# untitled.net
KiCad netlist of a schematic drawn in EAGLE
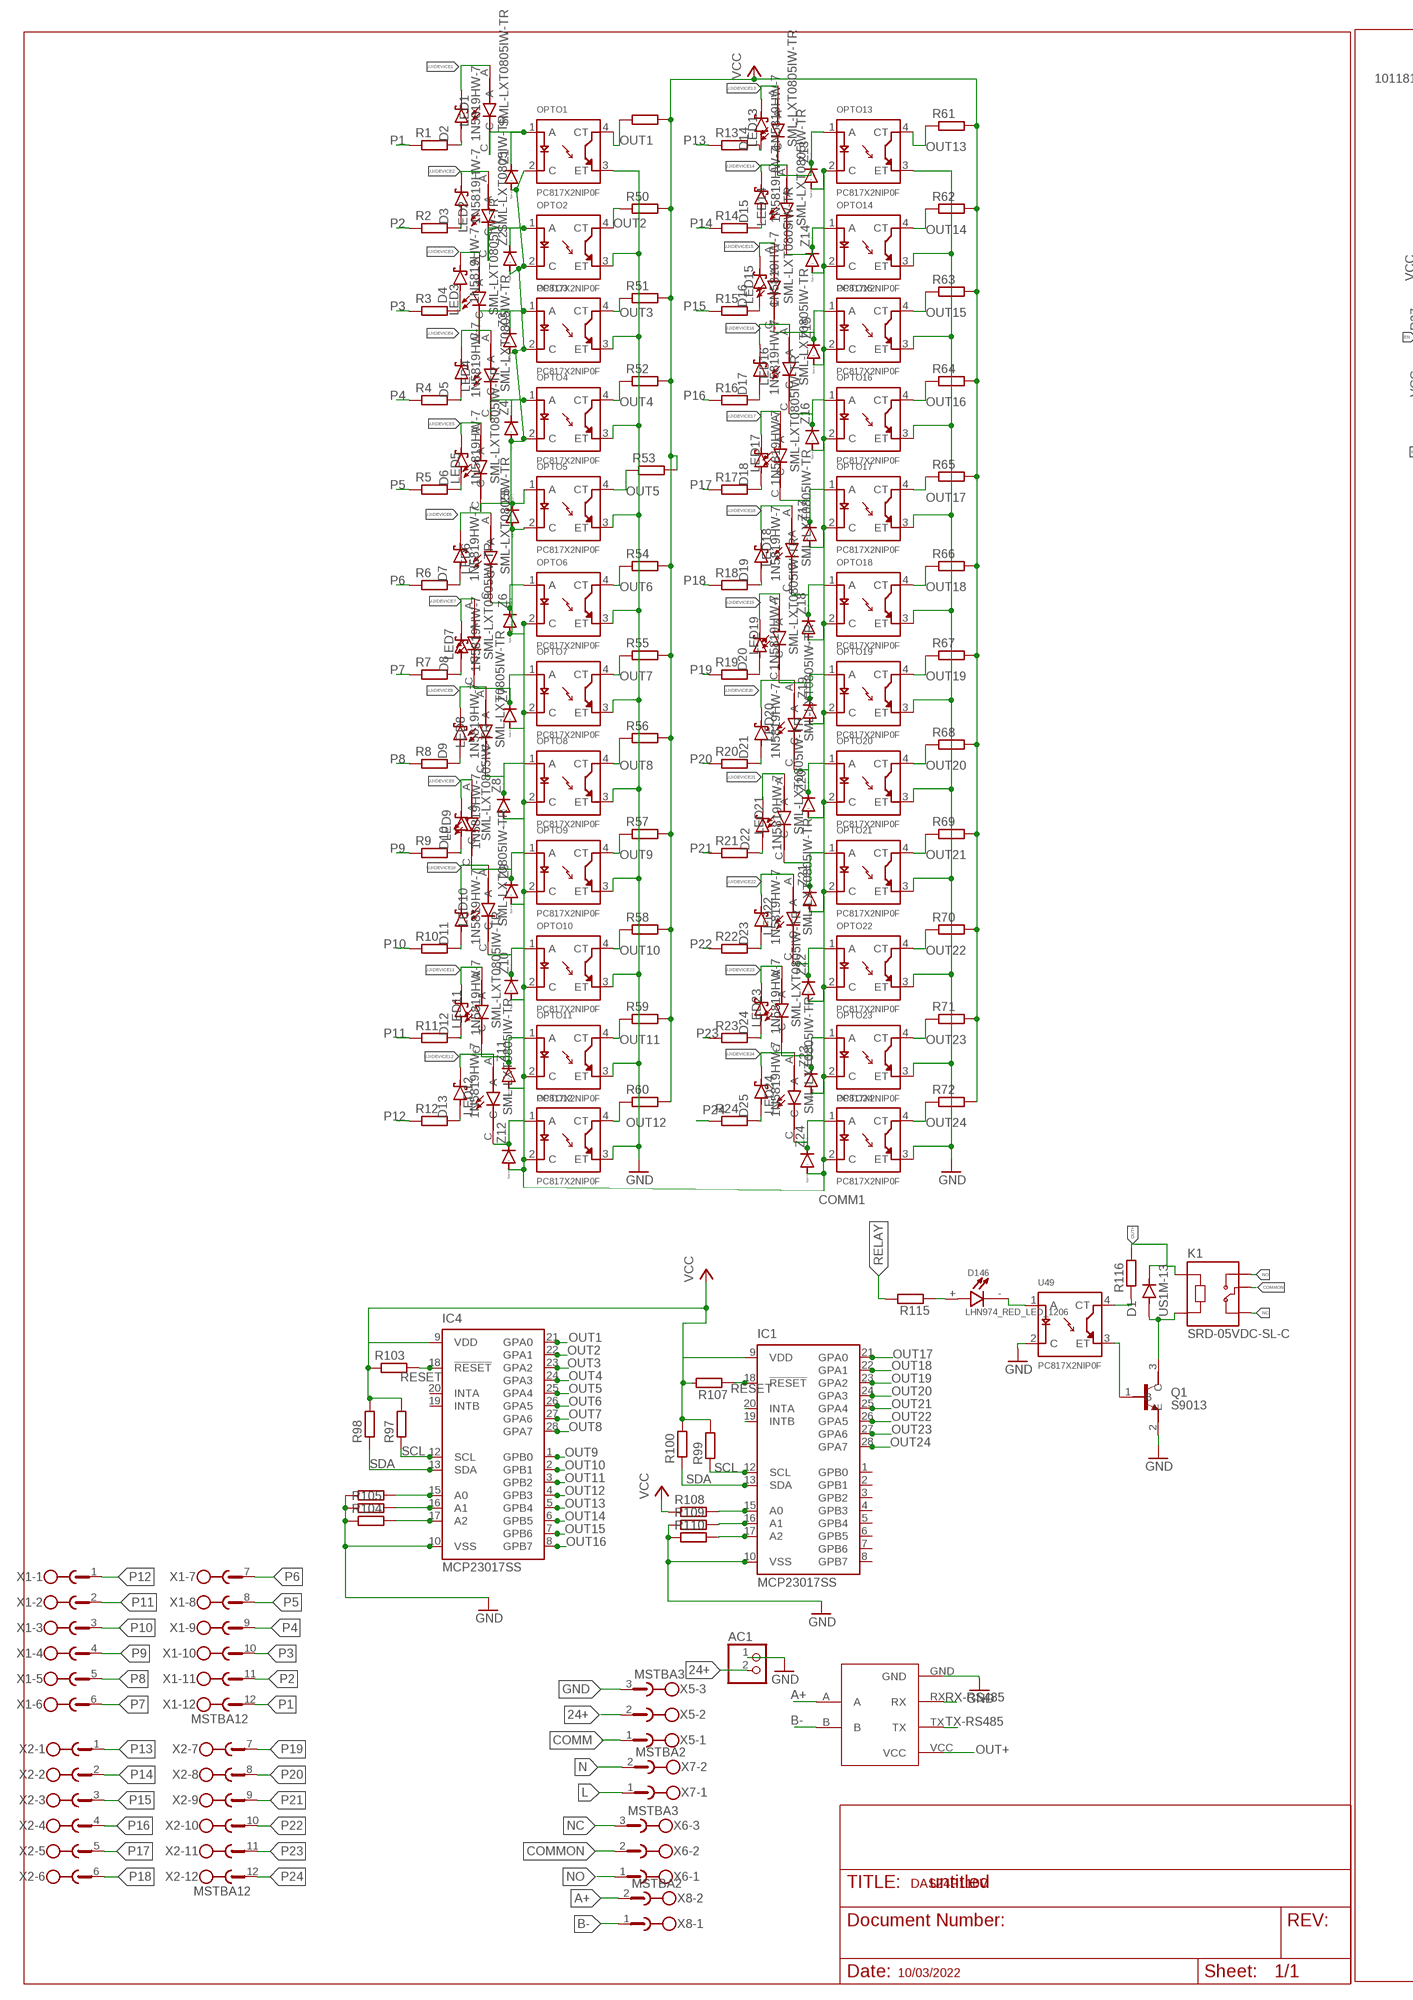
[diagram p0: schematic, sheet 1, part 1 of 2]
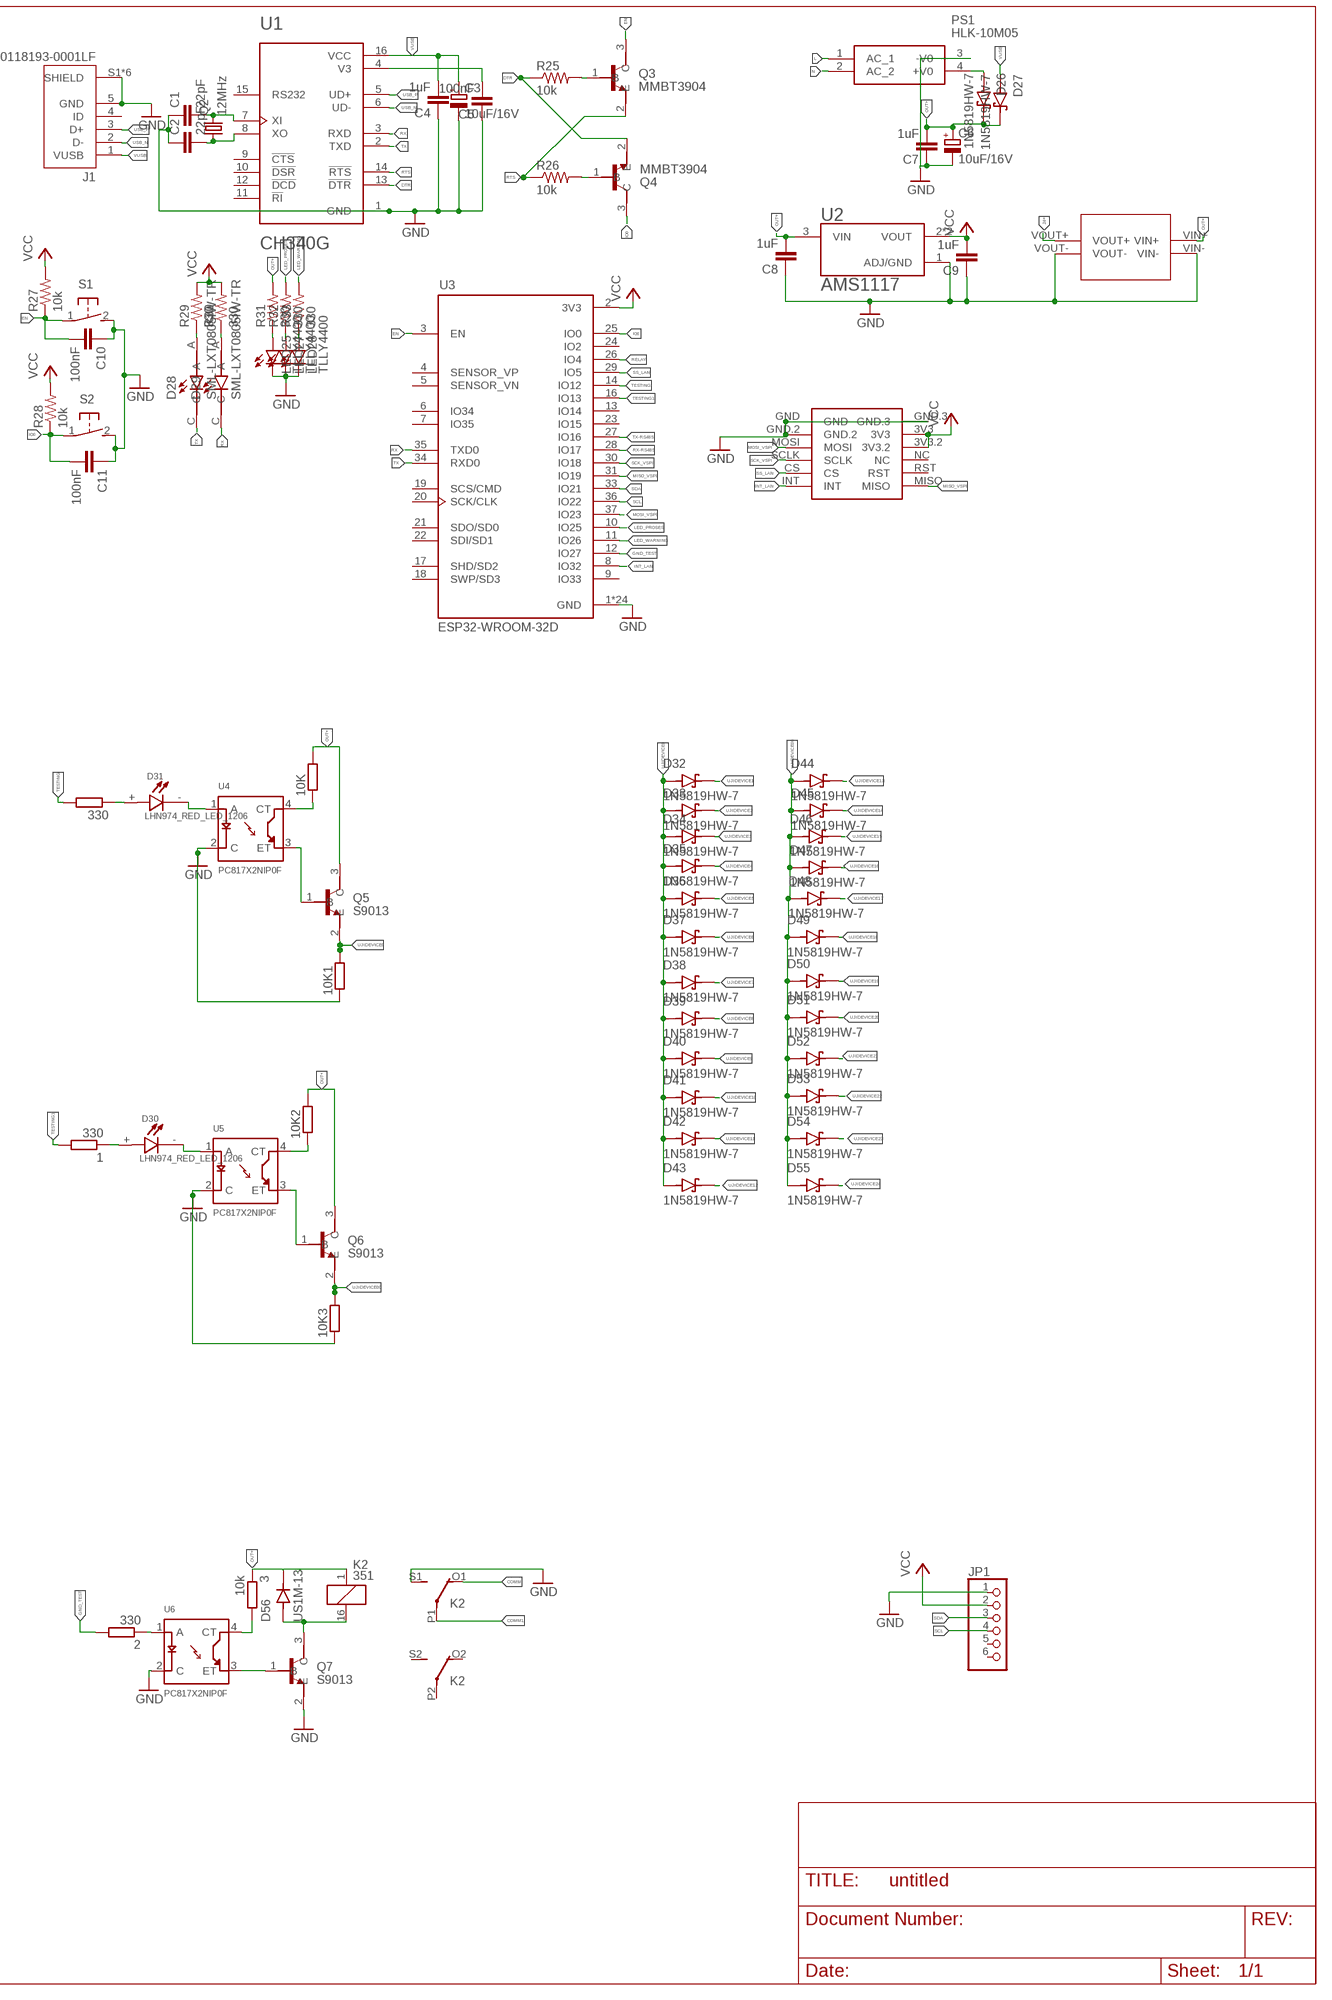
[diagram p1: schematic, sheet 1, part 2 of 2]

(export (version "E")
  (design (tool "Eeschema 10.0.6"))
  (components
    (comp (ref "1")
      (value "330")
      (footprint "eagle-import:R0805")
      (libsource (lib "eagle-import") (part "R-EU_R0805"))
    )
    (comp (ref "2")
      (value "330")
      (footprint "eagle-import:R0805")
      (libsource (lib "eagle-import") (part "R-EU_R0805"))
    )
    (comp (ref "3")
      (value "10k")
      (footprint "eagle-import:R0805")
      (libsource (lib "eagle-import") (part "R-EU_R0805"))
    )
    (comp (ref "10K")
      (value "R-EU_R0805")
      (footprint "eagle-import:R0805")
      (libsource (lib "eagle-import") (part "R-EU_R0805"))
    )
    (comp (ref "10K1")
      (value "R-EU_R0805")
      (footprint "eagle-import:R0805")
      (libsource (lib "eagle-import") (part "R-EU_R0805"))
    )
    (comp (ref "10K2")
      (value "R-EU_R0805")
      (footprint "eagle-import:R0805")
      (libsource (lib "eagle-import") (part "R-EU_R0805"))
    )
    (comp (ref "10K3")
      (value "R-EU_R0805")
      (footprint "eagle-import:R0805")
      (libsource (lib "eagle-import") (part "R-EU_R0805"))
    )
    (comp (ref "330")
      (value "R-EU_R0805")
      (footprint "eagle-import:R0805")
      (libsource (lib "eagle-import") (part "R-EU_R0805"))
    )
    (comp (ref "AC1")
      (value "PINHD-1X2")
      (footprint "eagle-import:1X02")
      (libsource (lib "eagle-import") (part "PINHD-1X2"))
    )
    (comp (ref "C1")
      (value "22pF")
      (footprint "eagle-import:C0805K")
      (libsource (lib "eagle-import") (part "C-EUC0805K"))
    )
    (comp (ref "C2")
      (value "22pF")
      (footprint "eagle-import:C0805K")
      (libsource (lib "eagle-import") (part "C-EUC0805K"))
    )
    (comp (ref "C3")
      (value "10uF/16V")
      (footprint "eagle-import:153CLV-0505")
      (libsource (lib "eagle-import") (part "CPOL-EU153CLV-0505"))
    )
    (comp (ref "C4")
      (value "1uF")
      (footprint "eagle-import:C0805K")
      (libsource (lib "eagle-import") (part "C-EUC0805K"))
    )
    (comp (ref "C5")
      (value "100nF")
      (footprint "eagle-import:C0805K")
      (libsource (lib "eagle-import") (part "C-EUC0805K"))
    )
    (comp (ref "C6")
      (value "10uF/16V")
      (footprint "eagle-import:153CLV-0505")
      (libsource (lib "eagle-import") (part "CPOL-EU153CLV-0505"))
    )
    (comp (ref "C7")
      (value "1uF")
      (footprint "eagle-import:C0805K")
      (libsource (lib "eagle-import") (part "C-EUC0805K"))
    )
    (comp (ref "C8")
      (value "1uF")
      (footprint "eagle-import:C0805K")
      (libsource (lib "eagle-import") (part "C-EUC0805K"))
    )
    (comp (ref "C9")
      (value "1uF")
      (footprint "eagle-import:C0805K")
      (libsource (lib "eagle-import") (part "C-EUC0805K"))
    )
    (comp (ref "C10")
      (value "100nF")
      (footprint "eagle-import:C0805K")
      (libsource (lib "eagle-import") (part "C-EUC0805K"))
    )
    (comp (ref "C11")
      (value "100nF")
      (footprint "eagle-import:C0805K")
      (libsource (lib "eagle-import") (part "C-EUC0805K"))
    )
    (comp (ref "D1")
      (value "US1M-13")
      (footprint "eagle-import:DIOM5226X240N")
      (fields (field (name "MF") "Diodes Incorporated"))
      (libsource (lib "eagle-import") (part "US1M-13"))
    )
    (comp (ref "D2")
      (value "1N5819HW-7")
      (footprint "eagle-import:SOD3715X145N")
      (fields (field (name "MF") "Diodes Inc."))
      (libsource (lib "eagle-import") (part "1N5819HW-7"))
    )
    (comp (ref "D3")
      (value "1N5819HW-7")
      (footprint "eagle-import:SOD3715X145N")
      (fields (field (name "MF") "Diodes Inc."))
      (libsource (lib "eagle-import") (part "1N5819HW-7"))
    )
    (comp (ref "D4")
      (value "1N5819HW-7")
      (footprint "eagle-import:SOD3715X145N")
      (fields (field (name "MF") "Diodes Inc."))
      (libsource (lib "eagle-import") (part "1N5819HW-7"))
    )
    (comp (ref "D5")
      (value "1N5819HW-7")
      (footprint "eagle-import:SOD3715X145N")
      (fields (field (name "MF") "Diodes Inc."))
      (libsource (lib "eagle-import") (part "1N5819HW-7"))
    )
    (comp (ref "D6")
      (value "1N5819HW-7")
      (footprint "eagle-import:SOD3715X145N")
      (fields (field (name "MF") "Diodes Inc."))
      (libsource (lib "eagle-import") (part "1N5819HW-7"))
    )
    (comp (ref "D7")
      (value "1N5819HW-7")
      (footprint "eagle-import:SOD3715X145N")
      (fields (field (name "MF") "Diodes Inc."))
      (libsource (lib "eagle-import") (part "1N5819HW-7"))
    )
    (comp (ref "D8")
      (value "1N5819HW-7")
      (footprint "eagle-import:SOD3715X145N")
      (fields (field (name "MF") "Diodes Inc."))
      (libsource (lib "eagle-import") (part "1N5819HW-7"))
    )
    (comp (ref "D9")
      (value "1N5819HW-7")
      (footprint "eagle-import:SOD3715X145N")
      (fields (field (name "MF") "Diodes Inc."))
      (libsource (lib "eagle-import") (part "1N5819HW-7"))
    )
    (comp (ref "D10")
      (value "1N5819HW-7")
      (footprint "eagle-import:SOD3715X145N")
      (fields (field (name "MF") "Diodes Inc."))
      (libsource (lib "eagle-import") (part "1N5819HW-7"))
    )
    (comp (ref "D11")
      (value "1N5819HW-7")
      (footprint "eagle-import:SOD3715X145N")
      (fields (field (name "MF") "Diodes Inc."))
      (libsource (lib "eagle-import") (part "1N5819HW-7"))
    )
    (comp (ref "D12")
      (value "1N5819HW-7")
      (footprint "eagle-import:SOD3715X145N")
      (fields (field (name "MF") "Diodes Inc."))
      (libsource (lib "eagle-import") (part "1N5819HW-7"))
    )
    (comp (ref "D13")
      (value "1N5819HW-7")
      (footprint "eagle-import:SOD3715X145N")
      (fields (field (name "MF") "Diodes Inc."))
      (libsource (lib "eagle-import") (part "1N5819HW-7"))
    )
    (comp (ref "D14")
      (value "1N5819HW-7")
      (footprint "eagle-import:SOD3715X145N")
      (fields (field (name "MF") "Diodes Inc."))
      (libsource (lib "eagle-import") (part "1N5819HW-7"))
    )
    (comp (ref "D15")
      (value "1N5819HW-7")
      (footprint "eagle-import:SOD3715X145N")
      (fields (field (name "MF") "Diodes Inc."))
      (libsource (lib "eagle-import") (part "1N5819HW-7"))
    )
    (comp (ref "D16")
      (value "1N5819HW-7")
      (footprint "eagle-import:SOD3715X145N")
      (fields (field (name "MF") "Diodes Inc."))
      (libsource (lib "eagle-import") (part "1N5819HW-7"))
    )
    (comp (ref "D17")
      (value "1N5819HW-7")
      (footprint "eagle-import:SOD3715X145N")
      (fields (field (name "MF") "Diodes Inc."))
      (libsource (lib "eagle-import") (part "1N5819HW-7"))
    )
    (comp (ref "D18")
      (value "1N5819HW-7")
      (footprint "eagle-import:SOD3715X145N")
      (fields (field (name "MF") "Diodes Inc."))
      (libsource (lib "eagle-import") (part "1N5819HW-7"))
    )
    (comp (ref "D19")
      (value "1N5819HW-7")
      (footprint "eagle-import:SOD3715X145N")
      (fields (field (name "MF") "Diodes Inc."))
      (libsource (lib "eagle-import") (part "1N5819HW-7"))
    )
    (comp (ref "D20")
      (value "1N5819HW-7")
      (footprint "eagle-import:SOD3715X145N")
      (fields (field (name "MF") "Diodes Inc."))
      (libsource (lib "eagle-import") (part "1N5819HW-7"))
    )
    (comp (ref "D21")
      (value "1N5819HW-7")
      (footprint "eagle-import:SOD3715X145N")
      (fields (field (name "MF") "Diodes Inc."))
      (libsource (lib "eagle-import") (part "1N5819HW-7"))
    )
    (comp (ref "D22")
      (value "1N5819HW-7")
      (footprint "eagle-import:SOD3715X145N")
      (fields (field (name "MF") "Diodes Inc."))
      (libsource (lib "eagle-import") (part "1N5819HW-7"))
    )
    (comp (ref "D23")
      (value "1N5819HW-7")
      (footprint "eagle-import:SOD3715X145N")
      (fields (field (name "MF") "Diodes Inc."))
      (libsource (lib "eagle-import") (part "1N5819HW-7"))
    )
    (comp (ref "D24")
      (value "1N5819HW-7")
      (footprint "eagle-import:SOD3715X145N")
      (fields (field (name "MF") "Diodes Inc."))
      (libsource (lib "eagle-import") (part "1N5819HW-7"))
    )
    (comp (ref "D25")
      (value "1N5819HW-7")
      (footprint "eagle-import:SOD3715X145N")
      (fields (field (name "MF") "Diodes Inc."))
      (libsource (lib "eagle-import") (part "1N5819HW-7"))
    )
    (comp (ref "D26")
      (value "1N5819HW-7")
      (footprint "eagle-import:SOD3715X145N")
      (fields (field (name "MF") "Diodes Inc."))
      (libsource (lib "eagle-import") (part "1N5819HW-7"))
    )
    (comp (ref "D27")
      (value "1N5819HW-7")
      (footprint "eagle-import:SOD3715X145N")
      (fields (field (name "MF") "Diodes Inc."))
      (libsource (lib "eagle-import") (part "1N5819HW-7"))
    )
    (comp (ref "D28")
      (value "SML-LXT0805IW-TR")
      (footprint "eagle-import:LEDC2012X120N")
      (fields (field (name "MF") "Lumex Opto/Components"))
      (libsource (lib "eagle-import") (part "SML-LXT0805IW-TR"))
    )
    (comp (ref "D29")
      (value "SML-LXT0805IW-TR")
      (footprint "eagle-import:LEDC2012X120N")
      (fields (field (name "MF") "Lumex Opto/Components"))
      (libsource (lib "eagle-import") (part "SML-LXT0805IW-TR"))
    )
    (comp (ref "D30")
      (value "LHN974_RED_LED_1206")
      (footprint "eagle-import:LEDC3216X120N")
      (fields (field (name "MF") "Osram") (field (name "MP") "LHN974 RED LED 1206"))
      (libsource (lib "eagle-import") (part "LHN974_RED_LED_1206"))
    )
    (comp (ref "D31")
      (value "LHN974_RED_LED_1206")
      (footprint "eagle-import:LEDC3216X120N")
      (fields (field (name "MF") "Osram") (field (name "MP") "LHN974 RED LED 1206"))
      (libsource (lib "eagle-import") (part "LHN974_RED_LED_1206"))
    )
    (comp (ref "D32")
      (value "1N5819HW-7")
      (footprint "eagle-import:SOD3715X145N")
      (fields (field (name "MF") "Diodes Inc."))
      (libsource (lib "eagle-import") (part "1N5819HW-7"))
    )
    (comp (ref "D33")
      (value "1N5819HW-7")
      (footprint "eagle-import:SOD3715X145N")
      (fields (field (name "MF") "Diodes Inc."))
      (libsource (lib "eagle-import") (part "1N5819HW-7"))
    )
    (comp (ref "D34")
      (value "1N5819HW-7")
      (footprint "eagle-import:SOD3715X145N")
      (fields (field (name "MF") "Diodes Inc."))
      (libsource (lib "eagle-import") (part "1N5819HW-7"))
    )
    (comp (ref "D35")
      (value "1N5819HW-7")
      (footprint "eagle-import:SOD3715X145N")
      (fields (field (name "MF") "Diodes Inc."))
      (libsource (lib "eagle-import") (part "1N5819HW-7"))
    )
    (comp (ref "D36")
      (value "1N5819HW-7")
      (footprint "eagle-import:SOD3715X145N")
      (fields (field (name "MF") "Diodes Inc."))
      (libsource (lib "eagle-import") (part "1N5819HW-7"))
    )
    (comp (ref "D37")
      (value "1N5819HW-7")
      (footprint "eagle-import:SOD3715X145N")
      (fields (field (name "MF") "Diodes Inc."))
      (libsource (lib "eagle-import") (part "1N5819HW-7"))
    )
    (comp (ref "D38")
      (value "1N5819HW-7")
      (footprint "eagle-import:SOD3715X145N")
      (fields (field (name "MF") "Diodes Inc."))
      (libsource (lib "eagle-import") (part "1N5819HW-7"))
    )
    (comp (ref "D39")
      (value "1N5819HW-7")
      (footprint "eagle-import:SOD3715X145N")
      (fields (field (name "MF") "Diodes Inc."))
      (libsource (lib "eagle-import") (part "1N5819HW-7"))
    )
    (comp (ref "D40")
      (value "1N5819HW-7")
      (footprint "eagle-import:SOD3715X145N")
      (fields (field (name "MF") "Diodes Inc."))
      (libsource (lib "eagle-import") (part "1N5819HW-7"))
    )
    (comp (ref "D41")
      (value "1N5819HW-7")
      (footprint "eagle-import:SOD3715X145N")
      (fields (field (name "MF") "Diodes Inc."))
      (libsource (lib "eagle-import") (part "1N5819HW-7"))
    )
    (comp (ref "D42")
      (value "1N5819HW-7")
      (footprint "eagle-import:SOD3715X145N")
      (fields (field (name "MF") "Diodes Inc."))
      (libsource (lib "eagle-import") (part "1N5819HW-7"))
    )
    (comp (ref "D43")
      (value "1N5819HW-7")
      (footprint "eagle-import:SOD3715X145N")
      (fields (field (name "MF") "Diodes Inc."))
      (libsource (lib "eagle-import") (part "1N5819HW-7"))
    )
    (comp (ref "D44")
      (value "1N5819HW-7")
      (footprint "eagle-import:SOD3715X145N")
      (fields (field (name "MF") "Diodes Inc."))
      (libsource (lib "eagle-import") (part "1N5819HW-7"))
    )
    (comp (ref "D45")
      (value "1N5819HW-7")
      (footprint "eagle-import:SOD3715X145N")
      (fields (field (name "MF") "Diodes Inc."))
      (libsource (lib "eagle-import") (part "1N5819HW-7"))
    )
    (comp (ref "D46")
      (value "1N5819HW-7")
      (footprint "eagle-import:SOD3715X145N")
      (fields (field (name "MF") "Diodes Inc."))
      (libsource (lib "eagle-import") (part "1N5819HW-7"))
    )
    (comp (ref "D47")
      (value "1N5819HW-7")
      (footprint "eagle-import:SOD3715X145N")
      (fields (field (name "MF") "Diodes Inc."))
      (libsource (lib "eagle-import") (part "1N5819HW-7"))
    )
    (comp (ref "D48")
      (value "1N5819HW-7")
      (footprint "eagle-import:SOD3715X145N")
      (fields (field (name "MF") "Diodes Inc."))
      (libsource (lib "eagle-import") (part "1N5819HW-7"))
    )
    (comp (ref "D49")
      (value "1N5819HW-7")
      (footprint "eagle-import:SOD3715X145N")
      (fields (field (name "MF") "Diodes Inc."))
      (libsource (lib "eagle-import") (part "1N5819HW-7"))
    )
    (comp (ref "D50")
      (value "1N5819HW-7")
      (footprint "eagle-import:SOD3715X145N")
      (fields (field (name "MF") "Diodes Inc."))
      (libsource (lib "eagle-import") (part "1N5819HW-7"))
    )
    (comp (ref "D51")
      (value "1N5819HW-7")
      (footprint "eagle-import:SOD3715X145N")
      (fields (field (name "MF") "Diodes Inc."))
      (libsource (lib "eagle-import") (part "1N5819HW-7"))
    )
    (comp (ref "D52")
      (value "1N5819HW-7")
      (footprint "eagle-import:SOD3715X145N")
      (fields (field (name "MF") "Diodes Inc."))
      (libsource (lib "eagle-import") (part "1N5819HW-7"))
    )
    (comp (ref "D53")
      (value "1N5819HW-7")
      (footprint "eagle-import:SOD3715X145N")
      (fields (field (name "MF") "Diodes Inc."))
      (libsource (lib "eagle-import") (part "1N5819HW-7"))
    )
    (comp (ref "D54")
      (value "1N5819HW-7")
      (footprint "eagle-import:SOD3715X145N")
      (fields (field (name "MF") "Diodes Inc."))
      (libsource (lib "eagle-import") (part "1N5819HW-7"))
    )
    (comp (ref "D55")
      (value "1N5819HW-7")
      (footprint "eagle-import:SOD3715X145N")
      (fields (field (name "MF") "Diodes Inc."))
      (libsource (lib "eagle-import") (part "1N5819HW-7"))
    )
    (comp (ref "D56")
      (value "US1M-13")
      (footprint "eagle-import:DIOM5226X240N")
      (fields (field (name "MF") "Diodes Incorporated"))
      (libsource (lib "eagle-import") (part "US1M-13"))
    )
    (comp (ref "D146")
      (value "LHN974_RED_LED_1206")
      (footprint "eagle-import:LEDC3216X120N")
      (fields (field (name "MF") "Osram") (field (name "MP") "LHN974 RED LED 1206"))
      (libsource (lib "eagle-import") (part "LHN974_RED_LED_1206"))
    )
    (comp (ref "IC1")
      (value "MCP23017SS")
      (footprint "eagle-import:SSOP28DB")
      (libsource (lib "eagle-import") (part "MCP23017SS"))
    )
    (comp (ref "IC4")
      (value "MCP23017SS")
      (footprint "eagle-import:SSOP28DB")
      (libsource (lib "eagle-import") (part "MCP23017SS"))
    )
    (comp (ref "J1")
      (value "10118193-0001LF")
      (footprint "eagle-import:FCI_10118193-0001LF")
      (fields (field (name "MF") "FCI"))
      (libsource (lib "eagle-import") (part "10118193-0001LF"))
    )
    (comp (ref "JP1")
      (value "PINHD-1X6CLEAN")
      (footprint "eagle-import:1X06-CLEAN")
      (libsource (lib "eagle-import") (part "PINHD-1X6CLEAN"))
    )
    (comp (ref "K1")
      (value "SRD-05VDC-SL-C")
      (footprint "eagle-import:RELAY_SRD-05VDC-SL-C")
      (fields (field (name "MF") "Songle Relay"))
      (libsource (lib "eagle-import") (part "SRD-05VDC-SL-C"))
    )
    (comp (ref "K2")
      (value "351")
      (footprint "eagle-import:351")
      (libsource (lib "eagle-import") (part "351"))
    )
    (comp (ref "LED1")
      (value "SML-LXT0805IW-TR")
      (footprint "eagle-import:LEDC2012X120N")
      (fields (field (name "MF") "Lumex Opto/Components"))
      (libsource (lib "eagle-import") (part "SML-LXT0805IW-TR"))
    )
    (comp (ref "LED2")
      (value "SML-LXT0805IW-TR")
      (footprint "eagle-import:LEDC2012X120N")
      (fields (field (name "MF") "Lumex Opto/Components"))
      (libsource (lib "eagle-import") (part "SML-LXT0805IW-TR"))
    )
    (comp (ref "LED3")
      (value "SML-LXT0805IW-TR")
      (footprint "eagle-import:LEDC2012X120N")
      (fields (field (name "MF") "Lumex Opto/Components"))
      (libsource (lib "eagle-import") (part "SML-LXT0805IW-TR"))
    )
    (comp (ref "LED4")
      (value "SML-LXT0805IW-TR")
      (footprint "eagle-import:LEDC2012X120N")
      (fields (field (name "MF") "Lumex Opto/Components"))
      (libsource (lib "eagle-import") (part "SML-LXT0805IW-TR"))
    )
    (comp (ref "LED5")
      (value "SML-LXT0805IW-TR")
      (footprint "eagle-import:LEDC2012X120N")
      (fields (field (name "MF") "Lumex Opto/Components"))
      (libsource (lib "eagle-import") (part "SML-LXT0805IW-TR"))
    )
    (comp (ref "LED6")
      (value "SML-LXT0805IW-TR")
      (footprint "eagle-import:LEDC2012X120N")
      (fields (field (name "MF") "Lumex Opto/Components"))
      (libsource (lib "eagle-import") (part "SML-LXT0805IW-TR"))
    )
    (comp (ref "LED7")
      (value "SML-LXT0805IW-TR")
      (footprint "eagle-import:LEDC2012X120N")
      (fields (field (name "MF") "Lumex Opto/Components"))
      (libsource (lib "eagle-import") (part "SML-LXT0805IW-TR"))
    )
    (comp (ref "LED8")
      (value "SML-LXT0805IW-TR")
      (footprint "eagle-import:LEDC2012X120N")
      (fields (field (name "MF") "Lumex Opto/Components"))
      (libsource (lib "eagle-import") (part "SML-LXT0805IW-TR"))
    )
    (comp (ref "LED9")
      (value "SML-LXT0805IW-TR")
      (footprint "eagle-import:LEDC2012X120N")
      (fields (field (name "MF") "Lumex Opto/Components"))
      (libsource (lib "eagle-import") (part "SML-LXT0805IW-TR"))
    )
    (comp (ref "LED10")
      (value "SML-LXT0805IW-TR")
      (footprint "eagle-import:LEDC2012X120N")
      (fields (field (name "MF") "Lumex Opto/Components"))
      (libsource (lib "eagle-import") (part "SML-LXT0805IW-TR"))
    )
    (comp (ref "LED11")
      (value "SML-LXT0805IW-TR")
      (footprint "eagle-import:LEDC2012X120N")
      (fields (field (name "MF") "Lumex Opto/Components"))
      (libsource (lib "eagle-import") (part "SML-LXT0805IW-TR"))
    )
    (comp (ref "LED12")
      (value "SML-LXT0805IW-TR")
      (footprint "eagle-import:LEDC2012X120N")
      (fields (field (name "MF") "Lumex Opto/Components"))
      (libsource (lib "eagle-import") (part "SML-LXT0805IW-TR"))
    )
    (comp (ref "LED13")
      (value "SML-LXT0805IW-TR")
      (footprint "eagle-import:LEDC2012X120N")
      (fields (field (name "MF") "Lumex Opto/Components"))
      (libsource (lib "eagle-import") (part "SML-LXT0805IW-TR"))
    )
    (comp (ref "LED14")
      (value "SML-LXT0805IW-TR")
      (footprint "eagle-import:LEDC2012X120N")
      (fields (field (name "MF") "Lumex Opto/Components"))
      (libsource (lib "eagle-import") (part "SML-LXT0805IW-TR"))
    )
    (comp (ref "LED15")
      (value "SML-LXT0805IW-TR")
      (footprint "eagle-import:LEDC2012X120N")
      (fields (field (name "MF") "Lumex Opto/Components"))
      (libsource (lib "eagle-import") (part "SML-LXT0805IW-TR"))
    )
    (comp (ref "LED16")
      (value "SML-LXT0805IW-TR")
      (footprint "eagle-import:LEDC2012X120N")
      (fields (field (name "MF") "Lumex Opto/Components"))
      (libsource (lib "eagle-import") (part "SML-LXT0805IW-TR"))
    )
    (comp (ref "LED17")
      (value "SML-LXT0805IW-TR")
      (footprint "eagle-import:LEDC2012X120N")
      (fields (field (name "MF") "Lumex Opto/Components"))
      (libsource (lib "eagle-import") (part "SML-LXT0805IW-TR"))
    )
    (comp (ref "LED18")
      (value "SML-LXT0805IW-TR")
      (footprint "eagle-import:LEDC2012X120N")
      (fields (field (name "MF") "Lumex Opto/Components"))
      (libsource (lib "eagle-import") (part "SML-LXT0805IW-TR"))
    )
    (comp (ref "LED19")
      (value "SML-LXT0805IW-TR")
      (footprint "eagle-import:LEDC2012X120N")
      (fields (field (name "MF") "Lumex Opto/Components"))
      (libsource (lib "eagle-import") (part "SML-LXT0805IW-TR"))
    )
    (comp (ref "LED20")
      (value "SML-LXT0805IW-TR")
      (footprint "eagle-import:LEDC2012X120N")
      (fields (field (name "MF") "Lumex Opto/Components"))
      (libsource (lib "eagle-import") (part "SML-LXT0805IW-TR"))
    )
    (comp (ref "LED21")
      (value "SML-LXT0805IW-TR")
      (footprint "eagle-import:LEDC2012X120N")
      (fields (field (name "MF") "Lumex Opto/Components"))
      (libsource (lib "eagle-import") (part "SML-LXT0805IW-TR"))
    )
    (comp (ref "LED22")
      (value "SML-LXT0805IW-TR")
      (footprint "eagle-import:LEDC2012X120N")
      (fields (field (name "MF") "Lumex Opto/Components"))
      (libsource (lib "eagle-import") (part "SML-LXT0805IW-TR"))
    )
    (comp (ref "LED23")
      (value "SML-LXT0805IW-TR")
      (footprint "eagle-import:LEDC2012X120N")
      (fields (field (name "MF") "Lumex Opto/Components"))
      (libsource (lib "eagle-import") (part "SML-LXT0805IW-TR"))
    )
    (comp (ref "LED24")
      (value "SML-LXT0805IW-TR")
      (footprint "eagle-import:LEDC2012X120N")
      (fields (field (name "MF") "Lumex Opto/Components"))
      (libsource (lib "eagle-import") (part "SML-LXT0805IW-TR"))
    )
    (comp (ref "LED25")
      (value "TLLY4400")
      (footprint "eagle-import:LED3MM")
      (fields (field (name "MF") "VISHAY SEMICONDUCTOR"))
      (libsource (lib "eagle-import") (part "TLLY4400"))
    )
    (comp (ref "LED27")
      (value "TLLY4400")
      (footprint "eagle-import:LED3MM")
      (fields (field (name "MF") "VISHAY SEMICONDUCTOR"))
      (libsource (lib "eagle-import") (part "TLLY4400"))
    )
    (comp (ref "LED28")
      (value "TLLY4400")
      (footprint "eagle-import:LED3MM")
      (fields (field (name "MF") "VISHAY SEMICONDUCTOR"))
      (libsource (lib "eagle-import") (part "TLLY4400"))
    )
    (comp (ref "MT1")
      (value "MT3608")
      (footprint "eagle-import:MT3608")
      (libsource (lib "eagle-import") (part "MT3608"))
    )
    (comp (ref "OPTO1")
      (value "PC817X2NIP0F")
      (footprint "eagle-import:SOT254P975X400-4N")
      (fields (field (name "MF") "Sharp Microelectronics"))
      (libsource (lib "eagle-import") (part "PC817X2NIP0F"))
    )
    (comp (ref "OPTO2")
      (value "PC817X2NIP0F")
      (footprint "eagle-import:SOT254P975X400-4N")
      (fields (field (name "MF") "Sharp Microelectronics"))
      (libsource (lib "eagle-import") (part "PC817X2NIP0F"))
    )
    (comp (ref "OPTO3")
      (value "PC817X2NIP0F")
      (footprint "eagle-import:SOT254P975X400-4N")
      (fields (field (name "MF") "Sharp Microelectronics"))
      (libsource (lib "eagle-import") (part "PC817X2NIP0F"))
    )
    (comp (ref "OPTO4")
      (value "PC817X2NIP0F")
      (footprint "eagle-import:SOT254P975X400-4N")
      (fields (field (name "MF") "Sharp Microelectronics"))
      (libsource (lib "eagle-import") (part "PC817X2NIP0F"))
    )
    (comp (ref "OPTO5")
      (value "PC817X2NIP0F")
      (footprint "eagle-import:SOT254P975X400-4N")
      (fields (field (name "MF") "Sharp Microelectronics"))
      (libsource (lib "eagle-import") (part "PC817X2NIP0F"))
    )
    (comp (ref "OPTO6")
      (value "PC817X2NIP0F")
      (footprint "eagle-import:SOT254P975X400-4N")
      (fields (field (name "MF") "Sharp Microelectronics"))
      (libsource (lib "eagle-import") (part "PC817X2NIP0F"))
    )
    (comp (ref "OPTO7")
      (value "PC817X2NIP0F")
      (footprint "eagle-import:SOT254P975X400-4N")
      (fields (field (name "MF") "Sharp Microelectronics"))
      (libsource (lib "eagle-import") (part "PC817X2NIP0F"))
    )
    (comp (ref "OPTO8")
      (value "PC817X2NIP0F")
      (footprint "eagle-import:SOT254P975X400-4N")
      (fields (field (name "MF") "Sharp Microelectronics"))
      (libsource (lib "eagle-import") (part "PC817X2NIP0F"))
    )
    (comp (ref "OPTO9")
      (value "PC817X2NIP0F")
      (footprint "eagle-import:SOT254P975X400-4N")
      (fields (field (name "MF") "Sharp Microelectronics"))
      (libsource (lib "eagle-import") (part "PC817X2NIP0F"))
    )
    (comp (ref "OPTO10")
      (value "PC817X2NIP0F")
      (footprint "eagle-import:SOT254P975X400-4N")
      (fields (field (name "MF") "Sharp Microelectronics"))
      (libsource (lib "eagle-import") (part "PC817X2NIP0F"))
    )
    (comp (ref "OPTO11")
      (value "PC817X2NIP0F")
      (footprint "eagle-import:SOT254P975X400-4N")
      (fields (field (name "MF") "Sharp Microelectronics"))
      (libsource (lib "eagle-import") (part "PC817X2NIP0F"))
    )
    (comp (ref "OPTO12")
      (value "PC817X2NIP0F")
      (footprint "eagle-import:SOT254P975X400-4N")
      (fields (field (name "MF") "Sharp Microelectronics"))
      (libsource (lib "eagle-import") (part "PC817X2NIP0F"))
    )
    (comp (ref "OPTO13")
      (value "PC817X2NIP0F")
      (footprint "eagle-import:SOT254P975X400-4N")
      (fields (field (name "MF") "Sharp Microelectronics"))
      (libsource (lib "eagle-import") (part "PC817X2NIP0F"))
    )
    (comp (ref "OPTO14")
      (value "PC817X2NIP0F")
      (footprint "eagle-import:SOT254P975X400-4N")
      (fields (field (name "MF") "Sharp Microelectronics"))
      (libsource (lib "eagle-import") (part "PC817X2NIP0F"))
    )
    (comp (ref "OPTO15")
      (value "PC817X2NIP0F")
      (footprint "eagle-import:SOT254P975X400-4N")
      (fields (field (name "MF") "Sharp Microelectronics"))
      (libsource (lib "eagle-import") (part "PC817X2NIP0F"))
    )
    (comp (ref "OPTO16")
      (value "PC817X2NIP0F")
      (footprint "eagle-import:SOT254P975X400-4N")
      (fields (field (name "MF") "Sharp Microelectronics"))
      (libsource (lib "eagle-import") (part "PC817X2NIP0F"))
    )
    (comp (ref "OPTO17")
      (value "PC817X2NIP0F")
      (footprint "eagle-import:SOT254P975X400-4N")
      (fields (field (name "MF") "Sharp Microelectronics"))
      (libsource (lib "eagle-import") (part "PC817X2NIP0F"))
    )
    (comp (ref "OPTO18")
      (value "PC817X2NIP0F")
      (footprint "eagle-import:SOT254P975X400-4N")
      (fields (field (name "MF") "Sharp Microelectronics"))
      (libsource (lib "eagle-import") (part "PC817X2NIP0F"))
    )
    (comp (ref "OPTO19")
      (value "PC817X2NIP0F")
      (footprint "eagle-import:SOT254P975X400-4N")
      (fields (field (name "MF") "Sharp Microelectronics"))
      (libsource (lib "eagle-import") (part "PC817X2NIP0F"))
    )
    (comp (ref "OPTO20")
      (value "PC817X2NIP0F")
      (footprint "eagle-import:SOT254P975X400-4N")
      (fields (field (name "MF") "Sharp Microelectronics"))
      (libsource (lib "eagle-import") (part "PC817X2NIP0F"))
    )
    (comp (ref "OPTO21")
      (value "PC817X2NIP0F")
      (footprint "eagle-import:SOT254P975X400-4N")
      (fields (field (name "MF") "Sharp Microelectronics"))
      (libsource (lib "eagle-import") (part "PC817X2NIP0F"))
    )
    (comp (ref "OPTO22")
      (value "PC817X2NIP0F")
      (footprint "eagle-import:SOT254P975X400-4N")
      (fields (field (name "MF") "Sharp Microelectronics"))
      (libsource (lib "eagle-import") (part "PC817X2NIP0F"))
    )
    (comp (ref "OPTO23")
      (value "PC817X2NIP0F")
      (footprint "eagle-import:SOT254P975X400-4N")
      (fields (field (name "MF") "Sharp Microelectronics"))
      (libsource (lib "eagle-import") (part "PC817X2NIP0F"))
    )
    (comp (ref "OPTO24")
      (value "PC817X2NIP0F")
      (footprint "eagle-import:SOT254P975X400-4N")
      (fields (field (name "MF") "Sharp Microelectronics"))
      (libsource (lib "eagle-import") (part "PC817X2NIP0F"))
    )
    (comp (ref "PS1")
      (value "HLK-10M05")
      (footprint "eagle-import:HLK10M05")
      (fields (field (name "MF") "Hi-link"))
      (libsource (lib "eagle-import") (part "HLK-10M05"))
    )
    (comp (ref "Q1")
      (value "S9013")
      (footprint "eagle-import:SOT95P240X120-3N")
      (fields (field (name "MF") "JCET"))
      (libsource (lib "eagle-import") (part "S9013"))
    )
    (comp (ref "Q2")
      (value "12MHz")
      (footprint "eagle-import:SM49")
      (libsource (lib "eagle-import") (part "CRYSTALSM49"))
    )
    (comp (ref "Q3")
      (value "MMBT3904")
      (footprint "eagle-import:SOT95P240X120-3N")
      (fields (field (name "MF") "ON Semiconductor"))
      (libsource (lib "eagle-import") (part "MMBT3904"))
    )
    (comp (ref "Q4")
      (value "MMBT3904")
      (footprint "eagle-import:SOT95P240X120-3N")
      (fields (field (name "MF") "ON Semiconductor"))
      (libsource (lib "eagle-import") (part "MMBT3904"))
    )
    (comp (ref "Q5")
      (value "S9013")
      (footprint "eagle-import:SOT95P240X120-3N")
      (fields (field (name "MF") "JCET"))
      (libsource (lib "eagle-import") (part "S9013"))
    )
    (comp (ref "Q6")
      (value "S9013")
      (footprint "eagle-import:SOT95P240X120-3N")
      (fields (field (name "MF") "JCET"))
      (libsource (lib "eagle-import") (part "S9013"))
    )
    (comp (ref "Q7")
      (value "S9013")
      (footprint "eagle-import:SOT95P240X120-3N")
      (fields (field (name "MF") "JCET"))
      (libsource (lib "eagle-import") (part "S9013"))
    )
    (comp (ref "R1")
      (value "R-EU_0414/15")
      (footprint "eagle-import:0414_15")
      (libsource (lib "eagle-import") (part "R-EU_0414/15"))
    )
    (comp (ref "R2")
      (value "R-EU_0414/15")
      (footprint "eagle-import:0414_15")
      (libsource (lib "eagle-import") (part "R-EU_0414/15"))
    )
    (comp (ref "R3")
      (value "R-EU_0414/15")
      (footprint "eagle-import:0414_15")
      (libsource (lib "eagle-import") (part "R-EU_0414/15"))
    )
    (comp (ref "R4")
      (value "R-EU_0414/15")
      (footprint "eagle-import:0414_15")
      (libsource (lib "eagle-import") (part "R-EU_0414/15"))
    )
    (comp (ref "R5")
      (value "R-EU_0414/15")
      (footprint "eagle-import:0414_15")
      (libsource (lib "eagle-import") (part "R-EU_0414/15"))
    )
    (comp (ref "R6")
      (value "R-EU_0414/15")
      (footprint "eagle-import:0414_15")
      (libsource (lib "eagle-import") (part "R-EU_0414/15"))
    )
    (comp (ref "R7")
      (value "R-EU_0414/15")
      (footprint "eagle-import:0414_15")
      (libsource (lib "eagle-import") (part "R-EU_0414/15"))
    )
    (comp (ref "R8")
      (value "R-EU_0414/15")
      (footprint "eagle-import:0414_15")
      (libsource (lib "eagle-import") (part "R-EU_0414/15"))
    )
    (comp (ref "R9")
      (value "R-EU_0414/15")
      (footprint "eagle-import:0414_15")
      (libsource (lib "eagle-import") (part "R-EU_0414/15"))
    )
    (comp (ref "R10")
      (value "R-EU_0414/15")
      (footprint "eagle-import:0414_15")
      (libsource (lib "eagle-import") (part "R-EU_0414/15"))
    )
    (comp (ref "R11")
      (value "R-EU_0414/15")
      (footprint "eagle-import:0414_15")
      (libsource (lib "eagle-import") (part "R-EU_0414/15"))
    )
    (comp (ref "R12")
      (value "R-EU_0414/15")
      (footprint "eagle-import:0414_15")
      (libsource (lib "eagle-import") (part "R-EU_0414/15"))
    )
    (comp (ref "R13")
      (value "R-EU_0414/15")
      (footprint "eagle-import:0414_15")
      (libsource (lib "eagle-import") (part "R-EU_0414/15"))
    )
    (comp (ref "R14")
      (value "R-EU_0414/15")
      (footprint "eagle-import:0414_15")
      (libsource (lib "eagle-import") (part "R-EU_0414/15"))
    )
    (comp (ref "R15")
      (value "R-EU_0414/15")
      (footprint "eagle-import:0414_15")
      (libsource (lib "eagle-import") (part "R-EU_0414/15"))
    )
    (comp (ref "R16")
      (value "R-EU_0414/15")
      (footprint "eagle-import:0414_15")
      (libsource (lib "eagle-import") (part "R-EU_0414/15"))
    )
    (comp (ref "R17")
      (value "R-EU_0414/15")
      (footprint "eagle-import:0414_15")
      (libsource (lib "eagle-import") (part "R-EU_0414/15"))
    )
    (comp (ref "R18")
      (value "R-EU_0414/15")
      (footprint "eagle-import:0414_15")
      (libsource (lib "eagle-import") (part "R-EU_0414/15"))
    )
    (comp (ref "R19")
      (value "R-EU_0414/15")
      (footprint "eagle-import:0414_15")
      (libsource (lib "eagle-import") (part "R-EU_0414/15"))
    )
    (comp (ref "R20")
      (value "R-EU_0414/15")
      (footprint "eagle-import:0414_15")
      (libsource (lib "eagle-import") (part "R-EU_0414/15"))
    )
    (comp (ref "R21")
      (value "R-EU_0414/15")
      (footprint "eagle-import:0414_15")
      (libsource (lib "eagle-import") (part "R-EU_0414/15"))
    )
    (comp (ref "R22")
      (value "R-EU_0414/15")
      (footprint "eagle-import:0414_15")
      (libsource (lib "eagle-import") (part "R-EU_0414/15"))
    )
    (comp (ref "R23")
      (value "R-EU_0414/15")
      (footprint "eagle-import:0414_15")
      (libsource (lib "eagle-import") (part "R-EU_0414/15"))
    )
    (comp (ref "R24")
      (value "R-EU_0414/15")
      (footprint "eagle-import:0414_15")
      (libsource (lib "eagle-import") (part "R-EU_0414/15"))
    )
    (comp (ref "R25")
      (value "10k")
      (footprint "eagle-import:M0805")
      (libsource (lib "eagle-import") (part "R-US_M0805"))
    )
    (comp (ref "R26")
      (value "10k")
      (footprint "eagle-import:M0805")
      (libsource (lib "eagle-import") (part "R-US_M0805"))
    )
    (comp (ref "R27")
      (value "10k")
      (footprint "eagle-import:M0805")
      (libsource (lib "eagle-import") (part "R-US_M0805"))
    )
    (comp (ref "R28")
      (value "10k")
      (footprint "eagle-import:M0805")
      (libsource (lib "eagle-import") (part "R-US_M0805"))
    )
    (comp (ref "R29")
      (value "330")
      (footprint "eagle-import:M0805")
      (libsource (lib "eagle-import") (part "R-US_M0805"))
    )
    (comp (ref "R30")
      (value "330")
      (footprint "eagle-import:M0805")
      (libsource (lib "eagle-import") (part "R-US_M0805"))
    )
    (comp (ref "R31")
      (value "330")
      (footprint "eagle-import:M0805")
      (libsource (lib "eagle-import") (part "R-US_M0805"))
    )
    (comp (ref "R32")
      (value "330")
      (footprint "eagle-import:M0805")
      (libsource (lib "eagle-import") (part "R-US_M0805"))
    )
    (comp (ref "R33")
      (value "330")
      (footprint "eagle-import:M0805")
      (libsource (lib "eagle-import") (part "R-US_M0805"))
    )
    (comp (ref "R49")
      (value "R-EU_R0805")
      (footprint "eagle-import:R0805")
      (libsource (lib "eagle-import") (part "R-EU_R0805"))
    )
    (comp (ref "R50")
      (value "R-EU_R0805")
      (footprint "eagle-import:R0805")
      (libsource (lib "eagle-import") (part "R-EU_R0805"))
    )
    (comp (ref "R51")
      (value "R-EU_R0805")
      (footprint "eagle-import:R0805")
      (libsource (lib "eagle-import") (part "R-EU_R0805"))
    )
    (comp (ref "R52")
      (value "R-EU_R0805")
      (footprint "eagle-import:R0805")
      (libsource (lib "eagle-import") (part "R-EU_R0805"))
    )
    (comp (ref "R53")
      (value "R-EU_R0805")
      (footprint "eagle-import:R0805")
      (libsource (lib "eagle-import") (part "R-EU_R0805"))
    )
    (comp (ref "R54")
      (value "R-EU_R0805")
      (footprint "eagle-import:R0805")
      (libsource (lib "eagle-import") (part "R-EU_R0805"))
    )
    (comp (ref "R55")
      (value "R-EU_R0805")
      (footprint "eagle-import:R0805")
      (libsource (lib "eagle-import") (part "R-EU_R0805"))
    )
    (comp (ref "R56")
      (value "R-EU_R0805")
      (footprint "eagle-import:R0805")
      (libsource (lib "eagle-import") (part "R-EU_R0805"))
    )
    (comp (ref "R57")
      (value "R-EU_R0805")
      (footprint "eagle-import:R0805")
      (libsource (lib "eagle-import") (part "R-EU_R0805"))
    )
    (comp (ref "R58")
      (value "R-EU_R0805")
      (footprint "eagle-import:R0805")
      (libsource (lib "eagle-import") (part "R-EU_R0805"))
    )
    (comp (ref "R59")
      (value "R-EU_R0805")
      (footprint "eagle-import:R0805")
      (libsource (lib "eagle-import") (part "R-EU_R0805"))
    )
    (comp (ref "R60")
      (value "R-EU_R0805")
      (footprint "eagle-import:R0805")
      (libsource (lib "eagle-import") (part "R-EU_R0805"))
    )
    (comp (ref "R61")
      (value "R-EU_R0805")
      (footprint "eagle-import:R0805")
      (libsource (lib "eagle-import") (part "R-EU_R0805"))
    )
    (comp (ref "R62")
      (value "R-EU_R0805")
      (footprint "eagle-import:R0805")
      (libsource (lib "eagle-import") (part "R-EU_R0805"))
    )
    (comp (ref "R63")
      (value "R-EU_R0805")
      (footprint "eagle-import:R0805")
      (libsource (lib "eagle-import") (part "R-EU_R0805"))
    )
    (comp (ref "R64")
      (value "R-EU_R0805")
      (footprint "eagle-import:R0805")
      (libsource (lib "eagle-import") (part "R-EU_R0805"))
    )
    (comp (ref "R65")
      (value "R-EU_R0805")
      (footprint "eagle-import:R0805")
      (libsource (lib "eagle-import") (part "R-EU_R0805"))
    )
    (comp (ref "R66")
      (value "R-EU_R0805")
      (footprint "eagle-import:R0805")
      (libsource (lib "eagle-import") (part "R-EU_R0805"))
    )
    (comp (ref "R67")
      (value "R-EU_R0805")
      (footprint "eagle-import:R0805")
      (libsource (lib "eagle-import") (part "R-EU_R0805"))
    )
    (comp (ref "R68")
      (value "R-EU_R0805")
      (footprint "eagle-import:R0805")
      (libsource (lib "eagle-import") (part "R-EU_R0805"))
    )
    (comp (ref "R69")
      (value "R-EU_R0805")
      (footprint "eagle-import:R0805")
      (libsource (lib "eagle-import") (part "R-EU_R0805"))
    )
    (comp (ref "R70")
      (value "R-EU_R0805")
      (footprint "eagle-import:R0805")
      (libsource (lib "eagle-import") (part "R-EU_R0805"))
    )
    (comp (ref "R71")
      (value "R-EU_R0805")
      (footprint "eagle-import:R0805")
      (libsource (lib "eagle-import") (part "R-EU_R0805"))
    )
    (comp (ref "R72")
      (value "R-EU_R0805")
      (footprint "eagle-import:R0805")
      (libsource (lib "eagle-import") (part "R-EU_R0805"))
    )
    (comp (ref "R97")
      (value "R-EU_R0805")
      (footprint "eagle-import:R0805")
      (libsource (lib "eagle-import") (part "R-EU_R0805"))
    )
    (comp (ref "R98")
      (value "R-EU_R0805")
      (footprint "eagle-import:R0805")
      (libsource (lib "eagle-import") (part "R-EU_R0805"))
    )
    (comp (ref "R99")
      (value "R-EU_R0805")
      (footprint "eagle-import:R0805")
      (libsource (lib "eagle-import") (part "R-EU_R0805"))
    )
    (comp (ref "R100")
      (value "R-EU_R0805")
      (footprint "eagle-import:R0805")
      (libsource (lib "eagle-import") (part "R-EU_R0805"))
    )
    (comp (ref "R103")
      (value "R-EU_R0805")
      (footprint "eagle-import:R0805")
      (libsource (lib "eagle-import") (part "R-EU_R0805"))
    )
    (comp (ref "R104")
      (value "R-EU_R0805")
      (footprint "eagle-import:R0805")
      (libsource (lib "eagle-import") (part "R-EU_R0805"))
    )
    (comp (ref "R105")
      (value "R-EU_R0805")
      (footprint "eagle-import:R0805")
      (libsource (lib "eagle-import") (part "R-EU_R0805"))
    )
    (comp (ref "R106")
      (value "R-EU_R0805")
      (footprint "eagle-import:R0805")
      (libsource (lib "eagle-import") (part "R-EU_R0805"))
    )
    (comp (ref "R107")
      (value "R-EU_R0805")
      (footprint "eagle-import:R0805")
      (libsource (lib "eagle-import") (part "R-EU_R0805"))
    )
    (comp (ref "R108")
      (value "R-EU_R0805")
      (footprint "eagle-import:R0805")
      (libsource (lib "eagle-import") (part "R-EU_R0805"))
    )
    (comp (ref "R109")
      (value "R-EU_R0805")
      (footprint "eagle-import:R0805")
      (libsource (lib "eagle-import") (part "R-EU_R0805"))
    )
    (comp (ref "R110")
      (value "R-EU_R0805")
      (footprint "eagle-import:R0805")
      (libsource (lib "eagle-import") (part "R-EU_R0805"))
    )
    (comp (ref "R115")
      (value "R-EU_R0805")
      (footprint "eagle-import:R0805")
      (libsource (lib "eagle-import") (part "R-EU_R0805"))
    )
    (comp (ref "R116")
      (value "R-EU_R0805")
      (footprint "eagle-import:R0805")
      (libsource (lib "eagle-import") (part "R-EU_R0805"))
    )
    (comp (ref "S1")
      (value "31-XX")
      (footprint "eagle-import:B3F-31XX")
      (fields (field (name "MPN") "B3F-3100"))
      (libsource (lib "eagle-import") (part "31-XX"))
    )
    (comp (ref "S2")
      (value "31-XX")
      (footprint "eagle-import:B3F-31XX")
      (fields (field (name "MPN") "B3F-3100"))
      (libsource (lib "eagle-import") (part "31-XX"))
    )
    (comp (ref "TTL-RS1")
      (value "TTL-RS485")
      (footprint "eagle-import:TTL-RS485")
      (libsource (lib "eagle-import") (part "TTL-RS485"))
    )
    (comp (ref "U$1")
      (value "MINI_W5500")
      (footprint "eagle-import:MINI_W5500")
      (libsource (lib "eagle-import") (part "MINI_W5500"))
    )
    (comp (ref "U1")
      (value "CH340G")
      (footprint "eagle-import:SOIC127P600X180-16N")
      (fields (field (name "MF") "WCH") (field (name "MP") "Ch340G"))
      (libsource (lib "eagle-import") (part "CH340G"))
    )
    (comp (ref "U2")
      (value "AMS1117")
      (footprint "eagle-import:SOT229P700X180-4N")
      (fields (field (name "MF") "Advanced Monolithic Systems"))
      (libsource (lib "eagle-import") (part "AMS1117"))
    )
    (comp (ref "U3")
      (value "ESP32-WROOM-32D")
      (footprint "eagle-import:MODULE_ESP32-WROOM-32D")
      (fields (field (name "MF") "Espressif Systems"))
      (libsource (lib "eagle-import") (part "ESP32-WROOM-32D"))
    )
    (comp (ref "U4")
      (value "PC817X2NIP0F")
      (footprint "eagle-import:SOT254P975X400-4N")
      (fields (field (name "MF") "Sharp Microelectronics"))
      (libsource (lib "eagle-import") (part "PC817X2NIP0F"))
    )
    (comp (ref "U5")
      (value "PC817X2NIP0F")
      (footprint "eagle-import:SOT254P975X400-4N")
      (fields (field (name "MF") "Sharp Microelectronics"))
      (libsource (lib "eagle-import") (part "PC817X2NIP0F"))
    )
    (comp (ref "U6")
      (value "PC817X2NIP0F")
      (footprint "eagle-import:SOT254P975X400-4N")
      (fields (field (name "MF") "Sharp Microelectronics"))
      (libsource (lib "eagle-import") (part "PC817X2NIP0F"))
    )
    (comp (ref "U49")
      (value "PC817X2NIP0F")
      (footprint "eagle-import:SOT254P975X400-4N")
      (fields (field (name "MF") "Sharp Microelectronics"))
      (libsource (lib "eagle-import") (part "PC817X2NIP0F"))
    )
    (comp (ref "X1")
      (value "MSTBA12")
      (footprint "eagle-import:MSTBA12")
      (fields (field (name "MPN") "1757349"))
      (libsource (lib "eagle-import") (part "MSTBA12"))
    )
    (comp (ref "X2")
      (value "MSTBA12")
      (footprint "eagle-import:MSTBA12")
      (fields (field (name "MPN") "1757349"))
      (libsource (lib "eagle-import") (part "MSTBA12"))
    )
    (comp (ref "X5")
      (value "MSTBA3")
      (footprint "eagle-import:MSTBA3")
      (fields (field (name "MF") "FARNELL") (field (name "MPN") "1757255"))
      (libsource (lib "eagle-import") (part "MSTBA3"))
    )
    (comp (ref "X6")
      (value "MSTBA3")
      (footprint "eagle-import:MSTBA3")
      (fields (field (name "MF") "FARNELL") (field (name "MPN") "1757255"))
      (libsource (lib "eagle-import") (part "MSTBA3"))
    )
    (comp (ref "X7")
      (value "MSTBA2")
      (footprint "eagle-import:MSTBA2")
      (fields (field (name "MF") "FARNELL") (field (name "MPN") "1757242"))
      (libsource (lib "eagle-import") (part "MSTBA2"))
    )
    (comp (ref "X8")
      (value "MSTBA2")
      (footprint "eagle-import:MSTBA2")
      (fields (field (name "MF") "FARNELL") (field (name "MPN") "1757242"))
      (libsource (lib "eagle-import") (part "MSTBA2"))
    )
    (comp (ref "Z1")
      (value "DIODE-SOD123")
      (footprint "eagle-import:SOD123")
      (libsource (lib "eagle-import") (part "DIODE-SOD123"))
    )
    (comp (ref "Z2")
      (value "DIODE-SOD123")
      (footprint "eagle-import:SOD123")
      (libsource (lib "eagle-import") (part "DIODE-SOD123"))
    )
    (comp (ref "Z3")
      (value "DIODE-SOD123")
      (footprint "eagle-import:SOD123")
      (libsource (lib "eagle-import") (part "DIODE-SOD123"))
    )
    (comp (ref "Z4")
      (value "DIODE-SOD123")
      (footprint "eagle-import:SOD123")
      (libsource (lib "eagle-import") (part "DIODE-SOD123"))
    )
    (comp (ref "Z5")
      (value "DIODE-SOD123")
      (footprint "eagle-import:SOD123")
      (libsource (lib "eagle-import") (part "DIODE-SOD123"))
    )
    (comp (ref "Z6")
      (value "DIODE-SOD123")
      (footprint "eagle-import:SOD123")
      (libsource (lib "eagle-import") (part "DIODE-SOD123"))
    )
    (comp (ref "Z7")
      (value "DIODE-SOD123")
      (footprint "eagle-import:SOD123")
      (libsource (lib "eagle-import") (part "DIODE-SOD123"))
    )
    (comp (ref "Z8")
      (value "DIODE-SOD123")
      (footprint "eagle-import:SOD123")
      (libsource (lib "eagle-import") (part "DIODE-SOD123"))
    )
    (comp (ref "Z9")
      (value "DIODE-SOD123")
      (footprint "eagle-import:SOD123")
      (libsource (lib "eagle-import") (part "DIODE-SOD123"))
    )
    (comp (ref "Z10")
      (value "DIODE-SOD123")
      (footprint "eagle-import:SOD123")
      (libsource (lib "eagle-import") (part "DIODE-SOD123"))
    )
    (comp (ref "Z11")
      (value "DIODE-SOD123")
      (footprint "eagle-import:SOD123")
      (libsource (lib "eagle-import") (part "DIODE-SOD123"))
    )
    (comp (ref "Z12")
      (value "DIODE-SOD123")
      (footprint "eagle-import:SOD123")
      (libsource (lib "eagle-import") (part "DIODE-SOD123"))
    )
    (comp (ref "Z13")
      (value "DIODE-SOD123")
      (footprint "eagle-import:SOD123")
      (libsource (lib "eagle-import") (part "DIODE-SOD123"))
    )
    (comp (ref "Z14")
      (value "DIODE-SOD123")
      (footprint "eagle-import:SOD123")
      (libsource (lib "eagle-import") (part "DIODE-SOD123"))
    )
    (comp (ref "Z15")
      (value "DIODE-SOD123")
      (footprint "eagle-import:SOD123")
      (libsource (lib "eagle-import") (part "DIODE-SOD123"))
    )
    (comp (ref "Z16")
      (value "DIODE-SOD123")
      (footprint "eagle-import:SOD123")
      (libsource (lib "eagle-import") (part "DIODE-SOD123"))
    )
    (comp (ref "Z17")
      (value "DIODE-SOD123")
      (footprint "eagle-import:SOD123")
      (libsource (lib "eagle-import") (part "DIODE-SOD123"))
    )
    (comp (ref "Z18")
      (value "DIODE-SOD123")
      (footprint "eagle-import:SOD123")
      (libsource (lib "eagle-import") (part "DIODE-SOD123"))
    )
    (comp (ref "Z19")
      (value "DIODE-SOD123")
      (footprint "eagle-import:SOD123")
      (libsource (lib "eagle-import") (part "DIODE-SOD123"))
    )
    (comp (ref "Z20")
      (value "DIODE-SOD123")
      (footprint "eagle-import:SOD123")
      (libsource (lib "eagle-import") (part "DIODE-SOD123"))
    )
    (comp (ref "Z21")
      (value "DIODE-SOD123")
      (footprint "eagle-import:SOD123")
      (libsource (lib "eagle-import") (part "DIODE-SOD123"))
    )
    (comp (ref "Z22")
      (value "DIODE-SOD123")
      (footprint "eagle-import:SOD123")
      (libsource (lib "eagle-import") (part "DIODE-SOD123"))
    )
    (comp (ref "Z23")
      (value "DIODE-SOD123")
      (footprint "eagle-import:SOD123")
      (libsource (lib "eagle-import") (part "DIODE-SOD123"))
    )
    (comp (ref "Z24")
      (value "DIODE-SOD123")
      (footprint "eagle-import:SOD123")
      (libsource (lib "eagle-import") (part "DIODE-SOD123"))
    )
  )
  (nets
    (net (code "1") (name "/OUT1") (class "Default")
      (node (ref "IC4") (pin "21") (pinfunction "GPA0_21") (pintype "bidirectional"))
      (node (ref "OPTO1") (pin "4") (pinfunction "CT_4") (pintype "passive"))
      (node (ref "R49") (pin "1") (pinfunction "1_1") (pintype "passive"))
    )
    (net (code "2") (name "/OUT2") (class "Default")
      (node (ref "IC4") (pin "22") (pinfunction "GPA1_22") (pintype "bidirectional"))
      (node (ref "OPTO2") (pin "4") (pinfunction "CT_4") (pintype "passive"))
      (node (ref "R50") (pin "1") (pinfunction "1_1") (pintype "passive"))
    )
    (net (code "3") (name "/OUT3") (class "Default")
      (node (ref "IC4") (pin "23") (pinfunction "GPA2_23") (pintype "bidirectional"))
      (node (ref "OPTO3") (pin "4") (pinfunction "CT_4") (pintype "passive"))
      (node (ref "R51") (pin "1") (pinfunction "1_1") (pintype "passive"))
    )
    (net (code "4") (name "/OUT4") (class "Default")
      (node (ref "IC4") (pin "24") (pinfunction "GPA3_24") (pintype "bidirectional"))
      (node (ref "OPTO4") (pin "4") (pinfunction "CT_4") (pintype "passive"))
      (node (ref "R52") (pin "1") (pinfunction "1_1") (pintype "passive"))
    )
    (net (code "5") (name "/OUT5") (class "Default")
      (node (ref "IC4") (pin "25") (pinfunction "GPA4_25") (pintype "bidirectional"))
      (node (ref "OPTO5") (pin "4") (pinfunction "CT_4") (pintype "passive"))
      (node (ref "R53") (pin "1") (pinfunction "1_1") (pintype "passive"))
    )
    (net (code "6") (name "/OUT6") (class "Default")
      (node (ref "IC4") (pin "26") (pinfunction "GPA5_26") (pintype "bidirectional"))
      (node (ref "OPTO6") (pin "4") (pinfunction "CT_4") (pintype "passive"))
      (node (ref "R54") (pin "1") (pinfunction "1_1") (pintype "passive"))
    )
    (net (code "7") (name "/OUT7") (class "Default")
      (node (ref "IC4") (pin "27") (pinfunction "GPA6_27") (pintype "bidirectional"))
      (node (ref "OPTO7") (pin "4") (pinfunction "CT_4") (pintype "passive"))
      (node (ref "R55") (pin "1") (pinfunction "1_1") (pintype "passive"))
    )
    (net (code "8") (name "/OUT8") (class "Default")
      (node (ref "IC4") (pin "28") (pinfunction "GPA7_28") (pintype "bidirectional"))
      (node (ref "OPTO8") (pin "4") (pinfunction "CT_4") (pintype "passive"))
      (node (ref "R56") (pin "1") (pinfunction "1_1") (pintype "passive"))
    )
    (net (code "9") (name "/OUT9") (class "Default")
      (node (ref "IC4") (pin "1") (pinfunction "GPB0_1") (pintype "bidirectional"))
      (node (ref "OPTO9") (pin "4") (pinfunction "CT_4") (pintype "passive"))
      (node (ref "R57") (pin "1") (pinfunction "1_1") (pintype "passive"))
    )
    (net (code "10") (name "/OUT10") (class "Default")
      (node (ref "IC4") (pin "2") (pinfunction "GPB1_2") (pintype "bidirectional"))
      (node (ref "OPTO10") (pin "4") (pinfunction "CT_4") (pintype "passive"))
      (node (ref "R58") (pin "1") (pinfunction "1_1") (pintype "passive"))
    )
    (net (code "11") (name "/OUT11") (class "Default")
      (node (ref "IC4") (pin "3") (pinfunction "GPB2_3") (pintype "bidirectional"))
      (node (ref "OPTO11") (pin "4") (pinfunction "CT_4") (pintype "passive"))
      (node (ref "R59") (pin "1") (pinfunction "1_1") (pintype "passive"))
    )
    (net (code "12") (name "/OUT12") (class "Default")
      (node (ref "IC4") (pin "4") (pinfunction "GPB3_4") (pintype "bidirectional"))
      (node (ref "OPTO12") (pin "4") (pinfunction "CT_4") (pintype "passive"))
      (node (ref "R60") (pin "1") (pinfunction "1_1") (pintype "passive"))
    )
    (net (code "13") (name "/OUT13") (class "Default")
      (node (ref "IC4") (pin "5") (pinfunction "GPB4_5") (pintype "bidirectional"))
      (node (ref "OPTO13") (pin "4") (pinfunction "CT_4") (pintype "passive"))
      (node (ref "R61") (pin "1") (pinfunction "1_1") (pintype "passive"))
    )
    (net (code "14") (name "/OUT14") (class "Default")
      (node (ref "IC4") (pin "6") (pinfunction "GPB5_6") (pintype "bidirectional"))
      (node (ref "OPTO14") (pin "4") (pinfunction "CT_4") (pintype "passive"))
      (node (ref "R62") (pin "1") (pinfunction "1_1") (pintype "passive"))
    )
    (net (code "15") (name "/OUT15") (class "Default")
      (node (ref "IC4") (pin "7") (pinfunction "GPB6_7") (pintype "bidirectional"))
      (node (ref "OPTO15") (pin "4") (pinfunction "CT_4") (pintype "passive"))
      (node (ref "R63") (pin "1") (pinfunction "1_1") (pintype "passive"))
    )
    (net (code "16") (name "/OUT16") (class "Default")
      (node (ref "IC4") (pin "8") (pinfunction "GPB7_8") (pintype "bidirectional"))
      (node (ref "OPTO16") (pin "4") (pinfunction "CT_4") (pintype "passive"))
      (node (ref "R64") (pin "1") (pinfunction "1_1") (pintype "passive"))
    )
    (net (code "17") (name "/OUT17") (class "Default")
      (node (ref "IC1") (pin "21") (pinfunction "GPA0_21") (pintype "bidirectional"))
      (node (ref "OPTO17") (pin "4") (pinfunction "CT_4") (pintype "passive"))
      (node (ref "R65") (pin "1") (pinfunction "1_1") (pintype "passive"))
    )
    (net (code "18") (name "/OUT18") (class "Default")
      (node (ref "IC1") (pin "22") (pinfunction "GPA1_22") (pintype "bidirectional"))
      (node (ref "OPTO18") (pin "4") (pinfunction "CT_4") (pintype "passive"))
      (node (ref "R66") (pin "1") (pinfunction "1_1") (pintype "passive"))
    )
    (net (code "19") (name "/OUT19") (class "Default")
      (node (ref "IC1") (pin "23") (pinfunction "GPA2_23") (pintype "bidirectional"))
      (node (ref "OPTO19") (pin "4") (pinfunction "CT_4") (pintype "passive"))
      (node (ref "R67") (pin "1") (pinfunction "1_1") (pintype "passive"))
    )
    (net (code "20") (name "/OUT20") (class "Default")
      (node (ref "IC1") (pin "24") (pinfunction "GPA3_24") (pintype "bidirectional"))
      (node (ref "OPTO20") (pin "4") (pinfunction "CT_4") (pintype "passive"))
      (node (ref "R68") (pin "1") (pinfunction "1_1") (pintype "passive"))
    )
    (net (code "21") (name "/OUT21") (class "Default")
      (node (ref "IC1") (pin "25") (pinfunction "GPA4_25") (pintype "bidirectional"))
      (node (ref "OPTO21") (pin "4") (pinfunction "CT_4") (pintype "passive"))
      (node (ref "R69") (pin "1") (pinfunction "1_1") (pintype "passive"))
    )
    (net (code "22") (name "/OUT22") (class "Default")
      (node (ref "IC1") (pin "26") (pinfunction "GPA5_26") (pintype "bidirectional"))
      (node (ref "OPTO22") (pin "4") (pinfunction "CT_4") (pintype "passive"))
      (node (ref "R70") (pin "1") (pinfunction "1_1") (pintype "passive"))
    )
    (net (code "23") (name "/OUT23") (class "Default")
      (node (ref "IC1") (pin "27") (pinfunction "GPA6_27") (pintype "bidirectional"))
      (node (ref "OPTO23") (pin "4") (pinfunction "CT_4") (pintype "passive"))
      (node (ref "R71") (pin "1") (pinfunction "1_1") (pintype "passive"))
    )
    (net (code "24") (name "/OUT24") (class "Default")
      (node (ref "IC1") (pin "28") (pinfunction "GPA7_28") (pintype "bidirectional"))
      (node (ref "OPTO24") (pin "4") (pinfunction "CT_4") (pintype "passive"))
      (node (ref "R72") (pin "1") (pinfunction "1_1") (pintype "passive"))
    )
    (net (code "25") (name "/RESET") (class "Default")
      (node (ref "IC1") (pin "18") (pinfunction "~{RESET}_18") (pintype "input"))
      (node (ref "IC4") (pin "18") (pinfunction "~{RESET}_18") (pintype "input"))
      (node (ref "R103") (pin "2") (pinfunction "2_2") (pintype "passive"))
      (node (ref "R107") (pin "1") (pinfunction "1_1") (pintype "passive"))
    )
    (net (code "26") (name "24+") (class "Default")
      (node (ref "AC1") (pin "2") (pinfunction "2_2") (pintype "passive"))
      (node (ref "MT1") (pin "VOUT+") (pinfunction "VOUT+_VOUT+") (pintype "bidirectional"))
      (node (ref "X5") (pin "2") (pinfunction "1_2") (pintype "passive"))
    )
    (net (code "27") (name "A+") (class "Default")
      (node (ref "TTL-RS1") (pin "A") (pinfunction "A_A") (pintype "bidirectional"))
      (node (ref "X8") (pin "2") (pinfunction "1_2") (pintype "passive"))
    )
    (net (code "28") (name "B-") (class "Default")
      (node (ref "TTL-RS1") (pin "B") (pinfunction "B_B") (pintype "bidirectional"))
      (node (ref "X8") (pin "1") (pinfunction "1_1") (pintype "passive"))
    )
    (net (code "29") (name "COMM") (class "Default")
      (node (ref "K2") (pin "O1") (pinfunction "O_O1") (pintype "passive"))
      (node (ref "X5") (pin "1") (pinfunction "1_1") (pintype "passive"))
    )
    (net (code "30") (name "COMM1") (class "Default")
      (node (ref "K2") (pin "P1") (pinfunction "P_P1") (pintype "passive"))
      (node (ref "OPTO1") (pin "2") (pinfunction "C_2") (pintype "passive"))
      (node (ref "OPTO10") (pin "2") (pinfunction "C_2") (pintype "passive"))
      (node (ref "OPTO11") (pin "2") (pinfunction "C_2") (pintype "passive"))
      (node (ref "OPTO12") (pin "2") (pinfunction "C_2") (pintype "passive"))
      (node (ref "OPTO13") (pin "2") (pinfunction "C_2") (pintype "passive"))
      (node (ref "OPTO14") (pin "2") (pinfunction "C_2") (pintype "passive"))
      (node (ref "OPTO15") (pin "2") (pinfunction "C_2") (pintype "passive"))
      (node (ref "OPTO16") (pin "2") (pinfunction "C_2") (pintype "passive"))
      (node (ref "OPTO17") (pin "2") (pinfunction "C_2") (pintype "passive"))
      (node (ref "OPTO18") (pin "2") (pinfunction "C_2") (pintype "passive"))
      (node (ref "OPTO19") (pin "2") (pinfunction "C_2") (pintype "passive"))
      (node (ref "OPTO2") (pin "2") (pinfunction "C_2") (pintype "passive"))
      (node (ref "OPTO20") (pin "2") (pinfunction "C_2") (pintype "passive"))
      (node (ref "OPTO21") (pin "2") (pinfunction "C_2") (pintype "passive"))
      (node (ref "OPTO22") (pin "2") (pinfunction "C_2") (pintype "passive"))
      (node (ref "OPTO23") (pin "2") (pinfunction "C_2") (pintype "passive"))
      (node (ref "OPTO24") (pin "2") (pinfunction "C_2") (pintype "passive"))
      (node (ref "OPTO3") (pin "2") (pinfunction "C_2") (pintype "passive"))
      (node (ref "OPTO4") (pin "2") (pinfunction "C_2") (pintype "passive"))
      (node (ref "OPTO5") (pin "2") (pinfunction "C_2") (pintype "passive"))
      (node (ref "OPTO6") (pin "2") (pinfunction "C_2") (pintype "passive"))
      (node (ref "OPTO7") (pin "2") (pinfunction "C_2") (pintype "passive"))
      (node (ref "OPTO8") (pin "2") (pinfunction "C_2") (pintype "passive"))
      (node (ref "OPTO9") (pin "2") (pinfunction "C_2") (pintype "passive"))
      (node (ref "Z1") (pin "A") (pinfunction "A_A") (pintype "passive"))
      (node (ref "Z10") (pin "A") (pinfunction "A_A") (pintype "passive"))
      (node (ref "Z11") (pin "A") (pinfunction "A_A") (pintype "passive"))
      (node (ref "Z12") (pin "A") (pinfunction "A_A") (pintype "passive"))
      (node (ref "Z13") (pin "A") (pinfunction "A_A") (pintype "passive"))
      (node (ref "Z14") (pin "A") (pinfunction "A_A") (pintype "passive"))
      (node (ref "Z15") (pin "A") (pinfunction "A_A") (pintype "passive"))
      (node (ref "Z16") (pin "A") (pinfunction "A_A") (pintype "passive"))
      (node (ref "Z17") (pin "A") (pinfunction "A_A") (pintype "passive"))
      (node (ref "Z18") (pin "A") (pinfunction "A_A") (pintype "passive"))
      (node (ref "Z19") (pin "A") (pinfunction "A_A") (pintype "passive"))
      (node (ref "Z2") (pin "A") (pinfunction "A_A") (pintype "passive"))
      (node (ref "Z20") (pin "A") (pinfunction "A_A") (pintype "passive"))
      (node (ref "Z21") (pin "A") (pinfunction "A_A") (pintype "passive"))
      (node (ref "Z22") (pin "A") (pinfunction "A_A") (pintype "passive"))
      (node (ref "Z23") (pin "A") (pinfunction "A_A") (pintype "passive"))
      (node (ref "Z24") (pin "A") (pinfunction "A_A") (pintype "passive"))
      (node (ref "Z3") (pin "A") (pinfunction "A_A") (pintype "passive"))
      (node (ref "Z4") (pin "A") (pinfunction "A_A") (pintype "passive"))
      (node (ref "Z5") (pin "A") (pinfunction "A_A") (pintype "passive"))
      (node (ref "Z6") (pin "A") (pinfunction "A_A") (pintype "passive"))
      (node (ref "Z7") (pin "A") (pinfunction "A_A") (pintype "passive"))
      (node (ref "Z8") (pin "A") (pinfunction "A_A") (pintype "passive"))
      (node (ref "Z9") (pin "A") (pinfunction "A_A") (pintype "passive"))
    )
    (net (code "31") (name "COMMON") (class "Default")
      (node (ref "K1") (pin "COM") (pinfunction "COM_COM") (pintype "passive"))
      (node (ref "X6") (pin "2") (pinfunction "1_2") (pintype "passive"))
    )
    (net (code "32") (name "DTR") (class "Default")
      (node (ref "Q4") (pin "2") (pinfunction "E_2") (pintype "passive"))
      (node (ref "R25") (pin "1") (pinfunction "1_1") (pintype "passive"))
      (node (ref "U1") (pin "13") (pinfunction "~{DTR}_13") (pintype "output"))
    )
    (net (code "33") (name "EN") (class "Default")
      (node (ref "C10") (pin "2") (pinfunction "2_2") (pintype "passive"))
      (node (ref "Q3") (pin "3") (pinfunction "C_3") (pintype "passive"))
      (node (ref "R27") (pin "1") (pinfunction "1_1") (pintype "passive"))
      (node (ref "S1") (pin "1") (pinfunction "P_1") (pintype "passive"))
      (node (ref "U3") (pin "3") (pinfunction "EN_3") (pintype "input"))
    )
    (net (code "34") (name "GND") (class "Default")
      (node (ref "10K1") (pin "1") (pinfunction "1_1") (pintype "passive"))
      (node (ref "10K3") (pin "1") (pinfunction "1_1") (pintype "passive"))
      (node (ref "AC1") (pin "1") (pinfunction "1_1") (pintype "passive"))
      (node (ref "C1") (pin "1") (pinfunction "1_1") (pintype "passive"))
      (node (ref "C10") (pin "1") (pinfunction "1_1") (pintype "passive"))
      (node (ref "C11") (pin "1") (pinfunction "1_1") (pintype "passive"))
      (node (ref "C2") (pin "1") (pinfunction "1_1") (pintype "passive"))
      (node (ref "C3") (pin "-") (pinfunction "-_-") (pintype "passive"))
      (node (ref "C4") (pin "1") (pinfunction "1_1") (pintype "passive"))
      (node (ref "C5") (pin "1") (pinfunction "1_1") (pintype "passive"))
      (node (ref "C6") (pin "-") (pinfunction "-_-") (pintype "passive"))
      (node (ref "C7") (pin "1") (pinfunction "1_1") (pintype "passive"))
      (node (ref "C8") (pin "1") (pinfunction "1_1") (pintype "passive"))
      (node (ref "C9") (pin "1") (pinfunction "1_1") (pintype "passive"))
      (node (ref "IC1") (pin "10") (pinfunction "VSS_10") (pintype "power_in"))
      (node (ref "IC4") (pin "10") (pinfunction "VSS_10") (pintype "power_in"))
      (node (ref "J1") (pin "5") (pinfunction "GND_5") (pintype "passive"))
      (node (ref "J1") (pin "S1") (pinfunction "SHIELD_S1") (pintype "passive"))
      (node (ref "J1") (pin "S2") (pinfunction "SHIELD_S2") (pintype "passive"))
      (node (ref "J1") (pin "S3") (pinfunction "SHIELD_S3") (pintype "passive"))
      (node (ref "J1") (pin "S4") (pinfunction "SHIELD_S4") (pintype "passive"))
      (node (ref "J1") (pin "S5") (pinfunction "SHIELD_S5") (pintype "passive"))
      (node (ref "J1") (pin "S6") (pinfunction "SHIELD_S6") (pintype "passive"))
      (node (ref "JP1") (pin "1") (pinfunction "1_1") (pintype "passive"))
      (node (ref "K2") (pin "S1") (pinfunction "S_S1") (pintype "passive"))
      (node (ref "LED25") (pin "K") (pinfunction "C_K") (pintype "passive"))
      (node (ref "LED27") (pin "K") (pinfunction "C_K") (pintype "passive"))
      (node (ref "LED28") (pin "K") (pinfunction "C_K") (pintype "passive"))
      (node (ref "MT1") (pin "VIN-") (pinfunction "VIN-_VIN-") (pintype "bidirectional"))
      (node (ref "MT1") (pin "VOUT-") (pinfunction "VOUT-_VOUT-") (pintype "bidirectional"))
      (node (ref "OPTO1") (pin "3") (pinfunction "ET_3") (pintype "passive"))
      (node (ref "OPTO10") (pin "3") (pinfunction "ET_3") (pintype "passive"))
      (node (ref "OPTO11") (pin "3") (pinfunction "ET_3") (pintype "passive"))
      (node (ref "OPTO12") (pin "3") (pinfunction "ET_3") (pintype "passive"))
      (node (ref "OPTO13") (pin "3") (pinfunction "ET_3") (pintype "passive"))
      (node (ref "OPTO14") (pin "3") (pinfunction "ET_3") (pintype "passive"))
      (node (ref "OPTO15") (pin "3") (pinfunction "ET_3") (pintype "passive"))
      (node (ref "OPTO16") (pin "3") (pinfunction "ET_3") (pintype "passive"))
      (node (ref "OPTO17") (pin "3") (pinfunction "ET_3") (pintype "passive"))
      (node (ref "OPTO18") (pin "3") (pinfunction "ET_3") (pintype "passive"))
      (node (ref "OPTO19") (pin "3") (pinfunction "ET_3") (pintype "passive"))
      (node (ref "OPTO2") (pin "3") (pinfunction "ET_3") (pintype "passive"))
      (node (ref "OPTO20") (pin "3") (pinfunction "ET_3") (pintype "passive"))
      (node (ref "OPTO21") (pin "3") (pinfunction "ET_3") (pintype "passive"))
      (node (ref "OPTO22") (pin "3") (pinfunction "ET_3") (pintype "passive"))
      (node (ref "OPTO23") (pin "3") (pinfunction "ET_3") (pintype "passive"))
      (node (ref "OPTO24") (pin "3") (pinfunction "ET_3") (pintype "passive"))
      (node (ref "OPTO3") (pin "3") (pinfunction "ET_3") (pintype "passive"))
      (node (ref "OPTO4") (pin "3") (pinfunction "ET_3") (pintype "passive"))
      (node (ref "OPTO5") (pin "3") (pinfunction "ET_3") (pintype "passive"))
      (node (ref "OPTO6") (pin "3") (pinfunction "ET_3") (pintype "passive"))
      (node (ref "OPTO7") (pin "3") (pinfunction "ET_3") (pintype "passive"))
      (node (ref "OPTO8") (pin "3") (pinfunction "ET_3") (pintype "passive"))
      (node (ref "OPTO9") (pin "3") (pinfunction "ET_3") (pintype "passive"))
      (node (ref "PS1") (pin "3") (pinfunction "-V0_3") (pintype "bidirectional"))
      (node (ref "Q1") (pin "2") (pinfunction "E_2") (pintype "passive"))
      (node (ref "Q7") (pin "2") (pinfunction "E_2") (pintype "passive"))
      (node (ref "R104") (pin "1") (pinfunction "1_1") (pintype "passive"))
      (node (ref "R105") (pin "1") (pinfunction "1_1") (pintype "passive"))
      (node (ref "R106") (pin "1") (pinfunction "1_1") (pintype "passive"))
      (node (ref "R109") (pin "1") (pinfunction "1_1") (pintype "passive"))
      (node (ref "R110") (pin "1") (pinfunction "1_1") (pintype "passive"))
      (node (ref "S1") (pin "2") (pinfunction "S_2") (pintype "passive"))
      (node (ref "S2") (pin "2") (pinfunction "S_2") (pintype "passive"))
      (node (ref "TTL-RS1") (pin "GND") (pinfunction "GND_GND") (pintype "bidirectional"))
      (node (ref "U$1") (pin "GND") (pinfunction "GND_GND") (pintype "bidirectional"))
      (node (ref "U$1") (pin "GND.2") (pinfunction "GND.2_GND.2") (pintype "bidirectional"))
      (node (ref "U$1") (pin "GND.3") (pinfunction "GND.3_GND.3") (pintype "bidirectional"))
      (node (ref "U1") (pin "1") (pinfunction "GND_1") (pintype "power_in"))
      (node (ref "U2") (pin "1") (pinfunction "ADJ/GND_1") (pintype "power_in"))
      (node (ref "U3") (pin "1") (pinfunction "GND_1") (pintype "power_in"))
      (node (ref "U3") (pin "15") (pinfunction "GND_15") (pintype "power_in"))
      (node (ref "U3") (pin "38") (pinfunction "GND_38") (pintype "power_in"))
      (node (ref "U3") (pin "39_1") (pinfunction "GND_39_1") (pintype "power_in"))
      (node (ref "U3") (pin "39_10") (pinfunction "GND_39_10") (pintype "power_in"))
      (node (ref "U3") (pin "39_11") (pinfunction "GND_39_11") (pintype "power_in"))
      (node (ref "U3") (pin "39_12") (pinfunction "GND_39_12") (pintype "power_in"))
      (node (ref "U3") (pin "39_13") (pinfunction "GND_39_13") (pintype "power_in"))
      (node (ref "U3") (pin "39_14") (pinfunction "GND_39_14") (pintype "power_in"))
      (node (ref "U3") (pin "39_15") (pinfunction "GND_39_15") (pintype "power_in"))
      (node (ref "U3") (pin "39_16") (pinfunction "GND_39_16") (pintype "power_in"))
      (node (ref "U3") (pin "39_17") (pinfunction "GND_39_17") (pintype "power_in"))
      (node (ref "U3") (pin "39_18") (pinfunction "GND_39_18") (pintype "power_in"))
      (node (ref "U3") (pin "39_19") (pinfunction "GND_39_19") (pintype "power_in"))
      (node (ref "U3") (pin "39_2") (pinfunction "GND_39_2") (pintype "power_in"))
      (node (ref "U3") (pin "39_20") (pinfunction "GND_39_20") (pintype "power_in"))
      (node (ref "U3") (pin "39_21") (pinfunction "GND_39_21") (pintype "power_in"))
      (node (ref "U3") (pin "39_3") (pinfunction "GND_39_3") (pintype "power_in"))
      (node (ref "U3") (pin "39_4") (pinfunction "GND_39_4") (pintype "power_in"))
      (node (ref "U3") (pin "39_5") (pinfunction "GND_39_5") (pintype "power_in"))
      (node (ref "U3") (pin "39_6") (pinfunction "GND_39_6") (pintype "power_in"))
      (node (ref "U3") (pin "39_7") (pinfunction "GND_39_7") (pintype "power_in"))
      (node (ref "U3") (pin "39_8") (pinfunction "GND_39_8") (pintype "power_in"))
      (node (ref "U3") (pin "39_9") (pinfunction "GND_39_9") (pintype "power_in"))
      (node (ref "U4") (pin "2") (pinfunction "C_2") (pintype "passive"))
      (node (ref "U49") (pin "2") (pinfunction "C_2") (pintype "passive"))
      (node (ref "U5") (pin "2") (pinfunction "C_2") (pintype "passive"))
      (node (ref "U6") (pin "2") (pinfunction "C_2") (pintype "passive"))
      (node (ref "X5") (pin "3") (pinfunction "1_3") (pintype "passive"))
    )
    (net (code "35") (name "GND_TEST") (class "Default")
      (node (ref "2") (pin "2") (pinfunction "2_2") (pintype "passive"))
      (node (ref "U3") (pin "12") (pinfunction "IO27_12") (pintype "bidirectional"))
    )
    (net (code "36") (name "INT_LAN") (class "Default")
      (node (ref "U$1") (pin "INT") (pinfunction "INT_INT") (pintype "bidirectional"))
      (node (ref "U3") (pin "8") (pinfunction "IO32_8") (pintype "bidirectional"))
    )
    (net (code "37") (name "IO0") (class "Default")
      (node (ref "C11") (pin "2") (pinfunction "2_2") (pintype "passive"))
      (node (ref "Q4") (pin "3") (pinfunction "C_3") (pintype "passive"))
      (node (ref "R28") (pin "1") (pinfunction "1_1") (pintype "passive"))
      (node (ref "S2") (pin "1") (pinfunction "P_1") (pintype "passive"))
      (node (ref "U3") (pin "25") (pinfunction "IO0_25") (pintype "bidirectional"))
    )
    (net (code "38") (name "L") (class "Default")
      (node (ref "PS1") (pin "1") (pinfunction "AC_1_1") (pintype "bidirectional"))
      (node (ref "X7") (pin "1") (pinfunction "1_1") (pintype "passive"))
    )
    (net (code "39") (name "LED_PROSES") (class "Default")
      (node (ref "R32") (pin "2") (pinfunction "2_2") (pintype "passive"))
      (node (ref "U3") (pin "10") (pinfunction "IO25_10") (pintype "bidirectional"))
    )
    (net (code "40") (name "LED_WARNING") (class "Default")
      (node (ref "R33") (pin "2") (pinfunction "2_2") (pintype "passive"))
      (node (ref "U3") (pin "11") (pinfunction "IO26_11") (pintype "bidirectional"))
    )
    (net (code "41") (name "MISO_VSPI") (class "Default")
      (node (ref "U$1") (pin "MISO") (pinfunction "MISO_MISO") (pintype "bidirectional"))
      (node (ref "U3") (pin "31") (pinfunction "IO19_31") (pintype "bidirectional"))
    )
    (net (code "42") (name "MOSI_VSPI") (class "Default")
      (node (ref "U$1") (pin "MOSI") (pinfunction "MOSI_MOSI") (pintype "bidirectional"))
      (node (ref "U3") (pin "37") (pinfunction "IO23_37") (pintype "bidirectional"))
    )
    (net (code "43") (name "N") (class "Default")
      (node (ref "PS1") (pin "2") (pinfunction "AC_2_2") (pintype "bidirectional"))
      (node (ref "X7") (pin "2") (pinfunction "1_2") (pintype "passive"))
    )
    (net (code "44") (name "NC") (class "Default")
      (node (ref "K1") (pin "NC") (pinfunction "NC_NC") (pintype "passive"))
      (node (ref "X6") (pin "3") (pinfunction "1_3") (pintype "passive"))
    )
    (net (code "45") (name "NO") (class "Default")
      (node (ref "K1") (pin "NO") (pinfunction "NO_NO") (pintype "passive"))
      (node (ref "X6") (pin "1") (pinfunction "1_1") (pintype "passive"))
    )
    (net (code "46") (name "Net-(1-Pad1)") (class "Default")
      (node (ref "1") (pin "1") (pinfunction "1_1") (pintype "passive"))
      (node (ref "D30") (pin "+") (pinfunction "+_+") (pintype "passive"))
    )
    (net (code "47") (name "Net-(330-Pad1)") (class "Default")
      (node (ref "330") (pin "1") (pinfunction "1_1") (pintype "passive"))
      (node (ref "D31") (pin "+") (pinfunction "+_+") (pintype "passive"))
    )
    (net (code "48") (name "Net-(D2-PadA)") (class "Default")
      (node (ref "D2") (pin "A") (pinfunction "A_A") (pintype "passive"))
      (node (ref "R1") (pin "2") (pinfunction "2_2") (pintype "passive"))
    )
    (net (code "49") (name "Net-(D3-PadA)") (class "Default")
      (node (ref "D3") (pin "A") (pinfunction "A_A") (pintype "passive"))
      (node (ref "R2") (pin "2") (pinfunction "2_2") (pintype "passive"))
    )
    (net (code "50") (name "Net-(D4-PadA)") (class "Default")
      (node (ref "D4") (pin "A") (pinfunction "A_A") (pintype "passive"))
      (node (ref "R3") (pin "2") (pinfunction "2_2") (pintype "passive"))
    )
    (net (code "51") (name "Net-(D5-PadA)") (class "Default")
      (node (ref "D5") (pin "A") (pinfunction "A_A") (pintype "passive"))
      (node (ref "R4") (pin "2") (pinfunction "2_2") (pintype "passive"))
    )
    (net (code "52") (name "Net-(D6-PadA)") (class "Default")
      (node (ref "D6") (pin "A") (pinfunction "A_A") (pintype "passive"))
      (node (ref "R5") (pin "2") (pinfunction "2_2") (pintype "passive"))
    )
    (net (code "53") (name "Net-(D7-PadA)") (class "Default")
      (node (ref "D7") (pin "A") (pinfunction "A_A") (pintype "passive"))
      (node (ref "R6") (pin "2") (pinfunction "2_2") (pintype "passive"))
    )
    (net (code "54") (name "Net-(D8-PadA)") (class "Default")
      (node (ref "D8") (pin "A") (pinfunction "A_A") (pintype "passive"))
      (node (ref "R7") (pin "2") (pinfunction "2_2") (pintype "passive"))
    )
    (net (code "55") (name "Net-(D9-PadA)") (class "Default")
      (node (ref "D9") (pin "A") (pinfunction "A_A") (pintype "passive"))
      (node (ref "R8") (pin "2") (pinfunction "2_2") (pintype "passive"))
    )
    (net (code "56") (name "Net-(D10-PadA)") (class "Default")
      (node (ref "D10") (pin "A") (pinfunction "A_A") (pintype "passive"))
      (node (ref "R9") (pin "2") (pinfunction "2_2") (pintype "passive"))
    )
    (net (code "57") (name "Net-(D11-PadA)") (class "Default")
      (node (ref "D11") (pin "A") (pinfunction "A_A") (pintype "passive"))
      (node (ref "R10") (pin "2") (pinfunction "2_2") (pintype "passive"))
    )
    (net (code "58") (name "Net-(D12-PadA)") (class "Default")
      (node (ref "D12") (pin "A") (pinfunction "A_A") (pintype "passive"))
      (node (ref "R11") (pin "2") (pinfunction "2_2") (pintype "passive"))
    )
    (net (code "59") (name "Net-(D13-PadA)") (class "Default")
      (node (ref "D13") (pin "A") (pinfunction "A_A") (pintype "passive"))
      (node (ref "R12") (pin "2") (pinfunction "2_2") (pintype "passive"))
    )
    (net (code "60") (name "Net-(D14-PadA)") (class "Default")
      (node (ref "D14") (pin "A") (pinfunction "A_A") (pintype "passive"))
      (node (ref "R13") (pin "2") (pinfunction "2_2") (pintype "passive"))
    )
    (net (code "61") (name "Net-(D15-PadA)") (class "Default")
      (node (ref "D15") (pin "A") (pinfunction "A_A") (pintype "passive"))
      (node (ref "R14") (pin "2") (pinfunction "2_2") (pintype "passive"))
    )
    (net (code "62") (name "Net-(D16-PadA)") (class "Default")
      (node (ref "D16") (pin "A") (pinfunction "A_A") (pintype "passive"))
      (node (ref "R15") (pin "2") (pinfunction "2_2") (pintype "passive"))
    )
    (net (code "63") (name "Net-(D17-PadA)") (class "Default")
      (node (ref "D17") (pin "A") (pinfunction "A_A") (pintype "passive"))
      (node (ref "R16") (pin "2") (pinfunction "2_2") (pintype "passive"))
    )
    (net (code "64") (name "Net-(D18-PadA)") (class "Default")
      (node (ref "D18") (pin "A") (pinfunction "A_A") (pintype "passive"))
      (node (ref "R17") (pin "2") (pinfunction "2_2") (pintype "passive"))
    )
    (net (code "65") (name "Net-(D19-PadA)") (class "Default")
      (node (ref "D19") (pin "A") (pinfunction "A_A") (pintype "passive"))
      (node (ref "R18") (pin "2") (pinfunction "2_2") (pintype "passive"))
    )
    (net (code "66") (name "Net-(D20-PadA)") (class "Default")
      (node (ref "D20") (pin "A") (pinfunction "A_A") (pintype "passive"))
      (node (ref "R19") (pin "2") (pinfunction "2_2") (pintype "passive"))
    )
    (net (code "67") (name "Net-(D21-PadA)") (class "Default")
      (node (ref "D21") (pin "A") (pinfunction "A_A") (pintype "passive"))
      (node (ref "R20") (pin "2") (pinfunction "2_2") (pintype "passive"))
    )
    (net (code "68") (name "Net-(D22-PadA)") (class "Default")
      (node (ref "D22") (pin "A") (pinfunction "A_A") (pintype "passive"))
      (node (ref "R21") (pin "2") (pinfunction "2_2") (pintype "passive"))
    )
    (net (code "69") (name "Net-(D23-PadA)") (class "Default")
      (node (ref "D23") (pin "A") (pinfunction "A_A") (pintype "passive"))
      (node (ref "R22") (pin "2") (pinfunction "2_2") (pintype "passive"))
    )
    (net (code "70") (name "Net-(D24-PadA)") (class "Default")
      (node (ref "D24") (pin "A") (pinfunction "A_A") (pintype "passive"))
      (node (ref "R23") (pin "2") (pinfunction "2_2") (pintype "passive"))
    )
    (net (code "71") (name "Net-(D25-PadA)") (class "Default")
      (node (ref "D25") (pin "A") (pinfunction "A_A") (pintype "passive"))
      (node (ref "R24") (pin "2") (pinfunction "2_2") (pintype "passive"))
    )
    (net (code "72") (name "Net-(D28-PadA)") (class "Default")
      (node (ref "D28") (pin "A") (pinfunction "A_A") (pintype "passive"))
      (node (ref "R29") (pin "1") (pinfunction "1_1") (pintype "passive"))
    )
    (net (code "73") (name "Net-(D29-PadA)") (class "Default")
      (node (ref "D29") (pin "A") (pinfunction "A_A") (pintype "passive"))
      (node (ref "R30") (pin "1") (pinfunction "1_1") (pintype "passive"))
    )
    (net (code "74") (name "Net-(D146-Pad+)") (class "Default")
      (node (ref "D146") (pin "+") (pinfunction "+_+") (pintype "passive"))
      (node (ref "R115") (pin "1") (pinfunction "1_1") (pintype "passive"))
    )
    (net (code "75") (name "Net-(IC1-A0)") (class "Default")
      (node (ref "IC1") (pin "15") (pinfunction "A0_15") (pintype "input"))
      (node (ref "R108") (pin "2") (pinfunction "2_2") (pintype "passive"))
    )
    (net (code "76") (name "Net-(IC1-A1)") (class "Default")
      (node (ref "IC1") (pin "16") (pinfunction "A1_16") (pintype "input"))
      (node (ref "R109") (pin "2") (pinfunction "2_2") (pintype "passive"))
    )
    (net (code "77") (name "Net-(IC1-A2)") (class "Default")
      (node (ref "IC1") (pin "17") (pinfunction "A2_17") (pintype "input"))
      (node (ref "R110") (pin "2") (pinfunction "2_2") (pintype "passive"))
    )
    (net (code "78") (name "Net-(IC4-A0)") (class "Default")
      (node (ref "IC4") (pin "15") (pinfunction "A0_15") (pintype "input"))
      (node (ref "R106") (pin "2") (pinfunction "2_2") (pintype "passive"))
    )
    (net (code "79") (name "Net-(IC4-A1)") (class "Default")
      (node (ref "IC4") (pin "16") (pinfunction "A1_16") (pintype "input"))
      (node (ref "R105") (pin "2") (pinfunction "2_2") (pintype "passive"))
    )
    (net (code "80") (name "Net-(IC4-A2)") (class "Default")
      (node (ref "IC4") (pin "17") (pinfunction "A2_17") (pintype "input"))
      (node (ref "R104") (pin "2") (pinfunction "2_2") (pintype "passive"))
    )
    (net (code "81") (name "Net-(K2A-2)") (class "Default")
      (node (ref "D56") (pin "A") (pinfunction "A_A") (pintype "passive"))
      (node (ref "K2") (pin "16") (pinfunction "2_16") (pintype "passive"))
      (node (ref "Q7") (pin "3") (pinfunction "C_3") (pintype "passive"))
    )
    (net (code "82") (name "Net-(LED25-PadA)") (class "Default")
      (node (ref "LED25") (pin "A") (pinfunction "A_A") (pintype "passive"))
      (node (ref "R31") (pin "1") (pinfunction "1_1") (pintype "passive"))
    )
    (net (code "83") (name "Net-(LED27-PadA)") (class "Default")
      (node (ref "LED27") (pin "A") (pinfunction "A_A") (pintype "passive"))
      (node (ref "R32") (pin "1") (pinfunction "1_1") (pintype "passive"))
    )
    (net (code "84") (name "Net-(LED28-PadA)") (class "Default")
      (node (ref "LED28") (pin "A") (pinfunction "A_A") (pintype "passive"))
      (node (ref "R33") (pin "1") (pinfunction "1_1") (pintype "passive"))
    )
    (net (code "85") (name "Net-(OPTO1-A)") (class "Default")
      (node (ref "LED1") (pin "C") (pinfunction "C_C") (pintype "passive"))
      (node (ref "OPTO1") (pin "1") (pinfunction "A_1") (pintype "passive"))
      (node (ref "Z1") (pin "C") (pinfunction "C_C") (pintype "passive"))
    )
    (net (code "86") (name "Net-(OPTO2-A)") (class "Default")
      (node (ref "LED2") (pin "C") (pinfunction "C_C") (pintype "passive"))
      (node (ref "OPTO2") (pin "1") (pinfunction "A_1") (pintype "passive"))
      (node (ref "Z2") (pin "C") (pinfunction "C_C") (pintype "passive"))
    )
    (net (code "87") (name "Net-(OPTO3-A)") (class "Default")
      (node (ref "LED3") (pin "C") (pinfunction "C_C") (pintype "passive"))
      (node (ref "OPTO3") (pin "1") (pinfunction "A_1") (pintype "passive"))
      (node (ref "Z3") (pin "C") (pinfunction "C_C") (pintype "passive"))
    )
    (net (code "88") (name "Net-(OPTO4-A)") (class "Default")
      (node (ref "LED4") (pin "C") (pinfunction "C_C") (pintype "passive"))
      (node (ref "OPTO4") (pin "1") (pinfunction "A_1") (pintype "passive"))
      (node (ref "Z4") (pin "C") (pinfunction "C_C") (pintype "passive"))
    )
    (net (code "89") (name "Net-(OPTO5-A)") (class "Default")
      (node (ref "LED5") (pin "C") (pinfunction "C_C") (pintype "passive"))
      (node (ref "OPTO5") (pin "1") (pinfunction "A_1") (pintype "passive"))
      (node (ref "Z5") (pin "C") (pinfunction "C_C") (pintype "passive"))
    )
    (net (code "90") (name "Net-(OPTO6-A)") (class "Default")
      (node (ref "LED6") (pin "C") (pinfunction "C_C") (pintype "passive"))
      (node (ref "OPTO6") (pin "1") (pinfunction "A_1") (pintype "passive"))
      (node (ref "Z6") (pin "C") (pinfunction "C_C") (pintype "passive"))
    )
    (net (code "91") (name "Net-(OPTO7-A)") (class "Default")
      (node (ref "LED7") (pin "C") (pinfunction "C_C") (pintype "passive"))
      (node (ref "OPTO7") (pin "1") (pinfunction "A_1") (pintype "passive"))
      (node (ref "Z7") (pin "C") (pinfunction "C_C") (pintype "passive"))
    )
    (net (code "92") (name "Net-(OPTO8-A)") (class "Default")
      (node (ref "LED8") (pin "C") (pinfunction "C_C") (pintype "passive"))
      (node (ref "OPTO8") (pin "1") (pinfunction "A_1") (pintype "passive"))
      (node (ref "Z8") (pin "C") (pinfunction "C_C") (pintype "passive"))
    )
    (net (code "93") (name "Net-(OPTO9-A)") (class "Default")
      (node (ref "LED9") (pin "C") (pinfunction "C_C") (pintype "passive"))
      (node (ref "OPTO9") (pin "1") (pinfunction "A_1") (pintype "passive"))
      (node (ref "Z9") (pin "C") (pinfunction "C_C") (pintype "passive"))
    )
    (net (code "94") (name "Net-(OPTO10-A)") (class "Default")
      (node (ref "LED10") (pin "C") (pinfunction "C_C") (pintype "passive"))
      (node (ref "OPTO10") (pin "1") (pinfunction "A_1") (pintype "passive"))
      (node (ref "Z10") (pin "C") (pinfunction "C_C") (pintype "passive"))
    )
    (net (code "95") (name "Net-(OPTO11-A)") (class "Default")
      (node (ref "LED11") (pin "C") (pinfunction "C_C") (pintype "passive"))
      (node (ref "OPTO11") (pin "1") (pinfunction "A_1") (pintype "passive"))
      (node (ref "Z11") (pin "C") (pinfunction "C_C") (pintype "passive"))
    )
    (net (code "96") (name "Net-(OPTO12-A)") (class "Default")
      (node (ref "LED12") (pin "C") (pinfunction "C_C") (pintype "passive"))
      (node (ref "OPTO12") (pin "1") (pinfunction "A_1") (pintype "passive"))
      (node (ref "Z12") (pin "C") (pinfunction "C_C") (pintype "passive"))
    )
    (net (code "97") (name "Net-(OPTO13-A)") (class "Default")
      (node (ref "LED13") (pin "C") (pinfunction "C_C") (pintype "passive"))
      (node (ref "OPTO13") (pin "1") (pinfunction "A_1") (pintype "passive"))
      (node (ref "Z13") (pin "C") (pinfunction "C_C") (pintype "passive"))
    )
    (net (code "98") (name "Net-(OPTO14-A)") (class "Default")
      (node (ref "LED14") (pin "C") (pinfunction "C_C") (pintype "passive"))
      (node (ref "OPTO14") (pin "1") (pinfunction "A_1") (pintype "passive"))
      (node (ref "Z14") (pin "C") (pinfunction "C_C") (pintype "passive"))
    )
    (net (code "99") (name "Net-(OPTO15-A)") (class "Default")
      (node (ref "LED15") (pin "C") (pinfunction "C_C") (pintype "passive"))
      (node (ref "OPTO15") (pin "1") (pinfunction "A_1") (pintype "passive"))
      (node (ref "Z15") (pin "C") (pinfunction "C_C") (pintype "passive"))
    )
    (net (code "100") (name "Net-(OPTO16-A)") (class "Default")
      (node (ref "LED16") (pin "C") (pinfunction "C_C") (pintype "passive"))
      (node (ref "OPTO16") (pin "1") (pinfunction "A_1") (pintype "passive"))
      (node (ref "Z16") (pin "C") (pinfunction "C_C") (pintype "passive"))
    )
    (net (code "101") (name "Net-(OPTO17-A)") (class "Default")
      (node (ref "LED17") (pin "C") (pinfunction "C_C") (pintype "passive"))
      (node (ref "OPTO17") (pin "1") (pinfunction "A_1") (pintype "passive"))
      (node (ref "Z17") (pin "C") (pinfunction "C_C") (pintype "passive"))
    )
    (net (code "102") (name "Net-(OPTO18-A)") (class "Default")
      (node (ref "LED18") (pin "C") (pinfunction "C_C") (pintype "passive"))
      (node (ref "OPTO18") (pin "1") (pinfunction "A_1") (pintype "passive"))
      (node (ref "Z18") (pin "C") (pinfunction "C_C") (pintype "passive"))
    )
    (net (code "103") (name "Net-(OPTO19-A)") (class "Default")
      (node (ref "LED19") (pin "C") (pinfunction "C_C") (pintype "passive"))
      (node (ref "OPTO19") (pin "1") (pinfunction "A_1") (pintype "passive"))
      (node (ref "Z19") (pin "C") (pinfunction "C_C") (pintype "passive"))
    )
    (net (code "104") (name "Net-(OPTO20-A)") (class "Default")
      (node (ref "LED20") (pin "C") (pinfunction "C_C") (pintype "passive"))
      (node (ref "OPTO20") (pin "1") (pinfunction "A_1") (pintype "passive"))
      (node (ref "Z20") (pin "C") (pinfunction "C_C") (pintype "passive"))
    )
    (net (code "105") (name "Net-(OPTO21-A)") (class "Default")
      (node (ref "LED21") (pin "C") (pinfunction "C_C") (pintype "passive"))
      (node (ref "OPTO21") (pin "1") (pinfunction "A_1") (pintype "passive"))
      (node (ref "Z21") (pin "C") (pinfunction "C_C") (pintype "passive"))
    )
    (net (code "106") (name "Net-(OPTO22-A)") (class "Default")
      (node (ref "LED22") (pin "C") (pinfunction "C_C") (pintype "passive"))
      (node (ref "OPTO22") (pin "1") (pinfunction "A_1") (pintype "passive"))
      (node (ref "Z22") (pin "C") (pinfunction "C_C") (pintype "passive"))
    )
    (net (code "107") (name "Net-(OPTO23-A)") (class "Default")
      (node (ref "LED23") (pin "C") (pinfunction "C_C") (pintype "passive"))
      (node (ref "OPTO23") (pin "1") (pinfunction "A_1") (pintype "passive"))
      (node (ref "Z23") (pin "C") (pinfunction "C_C") (pintype "passive"))
    )
    (net (code "108") (name "Net-(OPTO24-A)") (class "Default")
      (node (ref "LED24") (pin "C") (pinfunction "C_C") (pintype "passive"))
      (node (ref "OPTO24") (pin "1") (pinfunction "A_1") (pintype "passive"))
      (node (ref "Z24") (pin "C") (pinfunction "C_C") (pintype "passive"))
    )
    (net (code "109") (name "Net-(PS1-+V0)") (class "Default")
      (node (ref "D26") (pin "A") (pinfunction "A_A") (pintype "passive"))
      (node (ref "PS1") (pin "4") (pinfunction "+V0_4") (pintype "bidirectional"))
    )
    (net (code "110") (name "Net-(Q1-B)") (class "Default")
      (node (ref "Q1") (pin "1") (pinfunction "B_1") (pintype "passive"))
      (node (ref "U49") (pin "3") (pinfunction "ET_3") (pintype "passive"))
    )
    (net (code "111") (name "Net-(Q1-C)") (class "Default")
      (node (ref "D1") (pin "A") (pinfunction "A_A") (pintype "passive"))
      (node (ref "K1") (pin "A2") (pinfunction "A2_A2") (pintype "passive"))
      (node (ref "Q1") (pin "3") (pinfunction "C_3") (pintype "passive"))
    )
    (net (code "112") (name "Net-(Q3-B)") (class "Default")
      (node (ref "Q3") (pin "1") (pinfunction "B_1") (pintype "passive"))
      (node (ref "R25") (pin "2") (pinfunction "2_2") (pintype "passive"))
    )
    (net (code "113") (name "Net-(Q4-B)") (class "Default")
      (node (ref "Q4") (pin "1") (pinfunction "B_1") (pintype "passive"))
      (node (ref "R26") (pin "2") (pinfunction "2_2") (pintype "passive"))
    )
    (net (code "114") (name "Net-(Q5-B)") (class "Default")
      (node (ref "Q5") (pin "1") (pinfunction "B_1") (pintype "passive"))
      (node (ref "U4") (pin "3") (pinfunction "ET_3") (pintype "passive"))
    )
    (net (code "115") (name "Net-(Q6-B)") (class "Default")
      (node (ref "Q6") (pin "1") (pinfunction "B_1") (pintype "passive"))
      (node (ref "U5") (pin "3") (pinfunction "ET_3") (pintype "passive"))
    )
    (net (code "116") (name "Net-(Q7-B)") (class "Default")
      (node (ref "Q7") (pin "1") (pinfunction "B_1") (pintype "passive"))
      (node (ref "U6") (pin "3") (pinfunction "ET_3") (pintype "passive"))
    )
    (net (code "117") (name "Net-(U1-V3)") (class "Default")
      (node (ref "C5") (pin "2") (pinfunction "2_2") (pintype "passive"))
      (node (ref "U1") (pin "4") (pinfunction "V3_4") (pintype "power_in"))
    )
    (net (code "118") (name "Net-(U1-XI)") (class "Default")
      (node (ref "C1") (pin "2") (pinfunction "2_2") (pintype "passive"))
      (node (ref "Q2") (pin "2") (pinfunction "2_2") (pintype "passive"))
      (node (ref "U1") (pin "7") (pinfunction "XI_7") (pintype "input"))
    )
    (net (code "119") (name "Net-(U1-XO)") (class "Default")
      (node (ref "C2") (pin "2") (pinfunction "2_2") (pintype "passive"))
      (node (ref "Q2") (pin "1") (pinfunction "1_1") (pintype "passive"))
      (node (ref "U1") (pin "8") (pinfunction "XO_8") (pintype "output"))
    )
    (net (code "120") (name "Net-(U4-A)") (class "Default")
      (node (ref "D31") (pin "-") (pinfunction "-_-") (pintype "passive"))
      (node (ref "U4") (pin "1") (pinfunction "A_1") (pintype "passive"))
    )
    (net (code "121") (name "Net-(U4-CT)") (class "Default")
      (node (ref "10K") (pin "1") (pinfunction "1_1") (pintype "passive"))
      (node (ref "U4") (pin "4") (pinfunction "CT_4") (pintype "passive"))
    )
    (net (code "122") (name "Net-(U5-A)") (class "Default")
      (node (ref "D30") (pin "-") (pinfunction "-_-") (pintype "passive"))
      (node (ref "U5") (pin "1") (pinfunction "A_1") (pintype "passive"))
    )
    (net (code "123") (name "Net-(U5-CT)") (class "Default")
      (node (ref "10K2") (pin "1") (pinfunction "1_1") (pintype "passive"))
      (node (ref "U5") (pin "4") (pinfunction "CT_4") (pintype "passive"))
    )
    (net (code "124") (name "Net-(U6-A)") (class "Default")
      (node (ref "2") (pin "1") (pinfunction "1_1") (pintype "passive"))
      (node (ref "U6") (pin "1") (pinfunction "A_1") (pintype "passive"))
    )
    (net (code "125") (name "Net-(U6-CT)") (class "Default")
      (node (ref "3") (pin "2") (pinfunction "2_2") (pintype "passive"))
      (node (ref "U6") (pin "4") (pinfunction "CT_4") (pintype "passive"))
    )
    (net (code "126") (name "Net-(U49-A)") (class "Default")
      (node (ref "D146") (pin "-") (pinfunction "-_-") (pintype "passive"))
      (node (ref "U49") (pin "1") (pinfunction "A_1") (pintype "passive"))
    )
    (net (code "127") (name "Net-(U49-CT)") (class "Default")
      (node (ref "R116") (pin "1") (pinfunction "1_1") (pintype "passive"))
      (node (ref "U49") (pin "4") (pinfunction "CT_4") (pintype "passive"))
    )
    (net (code "128") (name "OUT+") (class "Default")
      (node (ref "10K") (pin "2") (pinfunction "2_2") (pintype "passive"))
      (node (ref "10K2") (pin "2") (pinfunction "2_2") (pintype "passive"))
      (node (ref "3") (pin "1") (pinfunction "1_1") (pintype "passive"))
      (node (ref "C6") (pin "+") (pinfunction "+_+") (pintype "passive"))
      (node (ref "C7") (pin "2") (pinfunction "2_2") (pintype "passive"))
      (node (ref "C8") (pin "2") (pinfunction "2_2") (pintype "passive"))
      (node (ref "D1") (pin "C") (pinfunction "K_C") (pintype "passive"))
      (node (ref "D26") (pin "C") (pinfunction "K_C") (pintype "passive"))
      (node (ref "D27") (pin "C") (pinfunction "K_C") (pintype "passive"))
      (node (ref "D56") (pin "C") (pinfunction "K_C") (pintype "passive"))
      (node (ref "K1") (pin "A1") (pinfunction "A1_A1") (pintype "passive"))
      (node (ref "K2") (pin "1") (pinfunction "1_1") (pintype "passive"))
      (node (ref "MT1") (pin "VIN+") (pinfunction "VIN+_VIN+") (pintype "bidirectional"))
      (node (ref "Q5") (pin "3") (pinfunction "C_3") (pintype "passive"))
      (node (ref "Q6") (pin "3") (pinfunction "C_3") (pintype "passive"))
      (node (ref "R116") (pin "2") (pinfunction "2_2") (pintype "passive"))
      (node (ref "R31") (pin "2") (pinfunction "2_2") (pintype "passive"))
      (node (ref "TTL-RS1") (pin "VCC") (pinfunction "VCC_VCC") (pintype "bidirectional"))
      (node (ref "U2") (pin "3") (pinfunction "VIN_3") (pintype "input"))
    )
    (net (code "129") (name "P1") (class "Default")
      (node (ref "R1") (pin "1") (pinfunction "1_1") (pintype "passive"))
      (node (ref "X1") (pin "12") (pinfunction "1_12") (pintype "passive"))
    )
    (net (code "130") (name "P2") (class "Default")
      (node (ref "R2") (pin "1") (pinfunction "1_1") (pintype "passive"))
      (node (ref "X1") (pin "11") (pinfunction "1_11") (pintype "passive"))
    )
    (net (code "131") (name "P3") (class "Default")
      (node (ref "R3") (pin "1") (pinfunction "1_1") (pintype "passive"))
      (node (ref "X1") (pin "10") (pinfunction "1_10") (pintype "passive"))
    )
    (net (code "132") (name "P4") (class "Default")
      (node (ref "R4") (pin "1") (pinfunction "1_1") (pintype "passive"))
      (node (ref "X1") (pin "9") (pinfunction "1_9") (pintype "passive"))
    )
    (net (code "133") (name "P5") (class "Default")
      (node (ref "R5") (pin "1") (pinfunction "1_1") (pintype "passive"))
      (node (ref "X1") (pin "8") (pinfunction "1_8") (pintype "passive"))
    )
    (net (code "134") (name "P6") (class "Default")
      (node (ref "R6") (pin "1") (pinfunction "1_1") (pintype "passive"))
      (node (ref "X1") (pin "7") (pinfunction "1_7") (pintype "passive"))
    )
    (net (code "135") (name "P7") (class "Default")
      (node (ref "R7") (pin "1") (pinfunction "1_1") (pintype "passive"))
      (node (ref "X1") (pin "6") (pinfunction "1_6") (pintype "passive"))
    )
    (net (code "136") (name "P8") (class "Default")
      (node (ref "R8") (pin "1") (pinfunction "1_1") (pintype "passive"))
      (node (ref "X1") (pin "5") (pinfunction "1_5") (pintype "passive"))
    )
    (net (code "137") (name "P9") (class "Default")
      (node (ref "R9") (pin "1") (pinfunction "1_1") (pintype "passive"))
      (node (ref "X1") (pin "4") (pinfunction "1_4") (pintype "passive"))
    )
    (net (code "138") (name "P10") (class "Default")
      (node (ref "R10") (pin "1") (pinfunction "1_1") (pintype "passive"))
      (node (ref "X1") (pin "3") (pinfunction "1_3") (pintype "passive"))
    )
    (net (code "139") (name "P11") (class "Default")
      (node (ref "R11") (pin "1") (pinfunction "1_1") (pintype "passive"))
      (node (ref "X1") (pin "2") (pinfunction "1_2") (pintype "passive"))
    )
    (net (code "140") (name "P12") (class "Default")
      (node (ref "R12") (pin "1") (pinfunction "1_1") (pintype "passive"))
      (node (ref "X1") (pin "1") (pinfunction "1_1") (pintype "passive"))
    )
    (net (code "141") (name "P13") (class "Default")
      (node (ref "R13") (pin "1") (pinfunction "1_1") (pintype "passive"))
      (node (ref "X2") (pin "1") (pinfunction "1_1") (pintype "passive"))
    )
    (net (code "142") (name "P14") (class "Default")
      (node (ref "R14") (pin "1") (pinfunction "1_1") (pintype "passive"))
      (node (ref "X2") (pin "2") (pinfunction "1_2") (pintype "passive"))
    )
    (net (code "143") (name "P15") (class "Default")
      (node (ref "R15") (pin "1") (pinfunction "1_1") (pintype "passive"))
      (node (ref "X2") (pin "3") (pinfunction "1_3") (pintype "passive"))
    )
    (net (code "144") (name "P16") (class "Default")
      (node (ref "R16") (pin "1") (pinfunction "1_1") (pintype "passive"))
      (node (ref "X2") (pin "4") (pinfunction "1_4") (pintype "passive"))
    )
    (net (code "145") (name "P17") (class "Default")
      (node (ref "R17") (pin "1") (pinfunction "1_1") (pintype "passive"))
      (node (ref "X2") (pin "5") (pinfunction "1_5") (pintype "passive"))
    )
    (net (code "146") (name "P18") (class "Default")
      (node (ref "R18") (pin "1") (pinfunction "1_1") (pintype "passive"))
      (node (ref "X2") (pin "6") (pinfunction "1_6") (pintype "passive"))
    )
    (net (code "147") (name "P19") (class "Default")
      (node (ref "R19") (pin "1") (pinfunction "1_1") (pintype "passive"))
      (node (ref "X2") (pin "7") (pinfunction "1_7") (pintype "passive"))
    )
    (net (code "148") (name "P20") (class "Default")
      (node (ref "R20") (pin "1") (pinfunction "1_1") (pintype "passive"))
      (node (ref "X2") (pin "8") (pinfunction "1_8") (pintype "passive"))
    )
    (net (code "149") (name "P21") (class "Default")
      (node (ref "R21") (pin "1") (pinfunction "1_1") (pintype "passive"))
      (node (ref "X2") (pin "9") (pinfunction "1_9") (pintype "passive"))
    )
    (net (code "150") (name "P22") (class "Default")
      (node (ref "R22") (pin "1") (pinfunction "1_1") (pintype "passive"))
      (node (ref "X2") (pin "10") (pinfunction "1_10") (pintype "passive"))
    )
    (net (code "151") (name "P23") (class "Default")
      (node (ref "R23") (pin "1") (pinfunction "1_1") (pintype "passive"))
      (node (ref "X2") (pin "11") (pinfunction "1_11") (pintype "passive"))
    )
    (net (code "152") (name "P24") (class "Default")
      (node (ref "R24") (pin "1") (pinfunction "1_1") (pintype "passive"))
      (node (ref "X2") (pin "12") (pinfunction "1_12") (pintype "passive"))
    )
    (net (code "153") (name "RELAY") (class "Default")
      (node (ref "R115") (pin "2") (pinfunction "2_2") (pintype "passive"))
      (node (ref "U3") (pin "26") (pinfunction "IO4_26") (pintype "bidirectional"))
    )
    (net (code "154") (name "RTS") (class "Default")
      (node (ref "Q3") (pin "2") (pinfunction "E_2") (pintype "passive"))
      (node (ref "R26") (pin "1") (pinfunction "1_1") (pintype "passive"))
      (node (ref "U1") (pin "14") (pinfunction "~{RTS}_14") (pintype "output"))
    )
    (net (code "155") (name "RX") (class "Default")
      (node (ref "D29") (pin "C") (pinfunction "C_C") (pintype "passive"))
      (node (ref "U1") (pin "3") (pinfunction "RXD_3") (pintype "input"))
      (node (ref "U3") (pin "35") (pinfunction "TXD0_35") (pintype "bidirectional"))
    )
    (net (code "156") (name "RX-RS485") (class "Default")
      (node (ref "TTL-RS1") (pin "RX") (pinfunction "RX_RX") (pintype "bidirectional"))
      (node (ref "U3") (pin "28") (pinfunction "IO17_28") (pintype "bidirectional"))
    )
    (net (code "157") (name "SCK_VSPI") (class "Default")
      (node (ref "U$1") (pin "SCLK") (pinfunction "SCLK_SCLK") (pintype "bidirectional"))
      (node (ref "U3") (pin "30") (pinfunction "IO18_30") (pintype "bidirectional"))
    )
    (net (code "158") (name "SCL") (class "Default")
      (node (ref "IC1") (pin "12") (pinfunction "SCL_12") (pintype "input"))
      (node (ref "IC4") (pin "12") (pinfunction "SCL_12") (pintype "input"))
      (node (ref "JP1") (pin "4") (pinfunction "4_4") (pintype "passive"))
      (node (ref "R97") (pin "1") (pinfunction "1_1") (pintype "passive"))
      (node (ref "R99") (pin "1") (pinfunction "1_1") (pintype "passive"))
      (node (ref "U3") (pin "36") (pinfunction "IO22_36") (pintype "bidirectional"))
    )
    (net (code "159") (name "SDA") (class "Default")
      (node (ref "IC1") (pin "13") (pinfunction "SDA_13") (pintype "bidirectional"))
      (node (ref "IC4") (pin "13") (pinfunction "SDA_13") (pintype "bidirectional"))
      (node (ref "JP1") (pin "3") (pinfunction "3_3") (pintype "passive"))
      (node (ref "R100") (pin "1") (pinfunction "1_1") (pintype "passive"))
      (node (ref "R98") (pin "1") (pinfunction "1_1") (pintype "passive"))
      (node (ref "U3") (pin "33") (pinfunction "IO21_33") (pintype "bidirectional"))
    )
    (net (code "160") (name "SS_LAN") (class "Default")
      (node (ref "U$1") (pin "CS") (pinfunction "CS_CS") (pintype "bidirectional"))
      (node (ref "U3") (pin "29") (pinfunction "IO5_29") (pintype "bidirectional"))
    )
    (net (code "161") (name "TESTING") (class "Default")
      (node (ref "330") (pin "2") (pinfunction "2_2") (pintype "passive"))
      (node (ref "U3") (pin "14") (pinfunction "IO12_14") (pintype "bidirectional"))
    )
    (net (code "162") (name "TESTING1") (class "Default")
      (node (ref "1") (pin "2") (pinfunction "2_2") (pintype "passive"))
      (node (ref "U3") (pin "16") (pinfunction "IO13_16") (pintype "bidirectional"))
    )
    (net (code "163") (name "TX") (class "Default")
      (node (ref "D28") (pin "C") (pinfunction "C_C") (pintype "passive"))
      (node (ref "U1") (pin "2") (pinfunction "TXD_2") (pintype "output"))
      (node (ref "U3") (pin "34") (pinfunction "RXD0_34") (pintype "bidirectional"))
    )
    (net (code "164") (name "TX-RS485") (class "Default")
      (node (ref "TTL-RS1") (pin "TX") (pinfunction "TX_TX") (pintype "bidirectional"))
      (node (ref "U3") (pin "27") (pinfunction "IO16_27") (pintype "bidirectional"))
    )
    (net (code "165") (name "UJIDEVICE00") (class "Default")
      (node (ref "10K3") (pin "2") (pinfunction "2_2") (pintype "passive"))
      (node (ref "D44") (pin "A") (pinfunction "A_A") (pintype "passive"))
      (node (ref "D45") (pin "A") (pinfunction "A_A") (pintype "passive"))
      (node (ref "D46") (pin "A") (pinfunction "A_A") (pintype "passive"))
      (node (ref "D47") (pin "A") (pinfunction "A_A") (pintype "passive"))
      (node (ref "D48") (pin "A") (pinfunction "A_A") (pintype "passive"))
      (node (ref "D49") (pin "A") (pinfunction "A_A") (pintype "passive"))
      (node (ref "D50") (pin "A") (pinfunction "A_A") (pintype "passive"))
      (node (ref "D51") (pin "A") (pinfunction "A_A") (pintype "passive"))
      (node (ref "D52") (pin "A") (pinfunction "A_A") (pintype "passive"))
      (node (ref "D53") (pin "A") (pinfunction "A_A") (pintype "passive"))
      (node (ref "D54") (pin "A") (pinfunction "A_A") (pintype "passive"))
      (node (ref "D55") (pin "A") (pinfunction "A_A") (pintype "passive"))
      (node (ref "Q6") (pin "2") (pinfunction "E_2") (pintype "passive"))
    )
    (net (code "166") (name "UJIDEVICE0") (class "Default")
      (node (ref "10K1") (pin "2") (pinfunction "2_2") (pintype "passive"))
      (node (ref "D32") (pin "A") (pinfunction "A_A") (pintype "passive"))
      (node (ref "D33") (pin "A") (pinfunction "A_A") (pintype "passive"))
      (node (ref "D34") (pin "A") (pinfunction "A_A") (pintype "passive"))
      (node (ref "D35") (pin "A") (pinfunction "A_A") (pintype "passive"))
      (node (ref "D36") (pin "A") (pinfunction "A_A") (pintype "passive"))
      (node (ref "D37") (pin "A") (pinfunction "A_A") (pintype "passive"))
      (node (ref "D38") (pin "A") (pinfunction "A_A") (pintype "passive"))
      (node (ref "D39") (pin "A") (pinfunction "A_A") (pintype "passive"))
      (node (ref "D40") (pin "A") (pinfunction "A_A") (pintype "passive"))
      (node (ref "D41") (pin "A") (pinfunction "A_A") (pintype "passive"))
      (node (ref "D42") (pin "A") (pinfunction "A_A") (pintype "passive"))
      (node (ref "D43") (pin "A") (pinfunction "A_A") (pintype "passive"))
      (node (ref "Q5") (pin "2") (pinfunction "E_2") (pintype "passive"))
    )
    (net (code "167") (name "UJIDEVICE1") (class "Default")
      (node (ref "D2") (pin "C") (pinfunction "K_C") (pintype "passive"))
      (node (ref "D32") (pin "C") (pinfunction "K_C") (pintype "passive"))
      (node (ref "LED1") (pin "A") (pinfunction "A_A") (pintype "passive"))
    )
    (net (code "168") (name "UJIDEVICE2") (class "Default")
      (node (ref "D3") (pin "C") (pinfunction "K_C") (pintype "passive"))
      (node (ref "D33") (pin "C") (pinfunction "K_C") (pintype "passive"))
      (node (ref "LED2") (pin "A") (pinfunction "A_A") (pintype "passive"))
    )
    (net (code "169") (name "UJIDEVICE3") (class "Default")
      (node (ref "D34") (pin "C") (pinfunction "K_C") (pintype "passive"))
      (node (ref "D4") (pin "C") (pinfunction "K_C") (pintype "passive"))
      (node (ref "LED3") (pin "A") (pinfunction "A_A") (pintype "passive"))
    )
    (net (code "170") (name "UJIDEVICE4") (class "Default")
      (node (ref "D35") (pin "C") (pinfunction "K_C") (pintype "passive"))
      (node (ref "D5") (pin "C") (pinfunction "K_C") (pintype "passive"))
      (node (ref "LED4") (pin "A") (pinfunction "A_A") (pintype "passive"))
    )
    (net (code "171") (name "UJIDEVICE5") (class "Default")
      (node (ref "D36") (pin "C") (pinfunction "K_C") (pintype "passive"))
      (node (ref "D6") (pin "C") (pinfunction "K_C") (pintype "passive"))
      (node (ref "LED5") (pin "A") (pinfunction "A_A") (pintype "passive"))
    )
    (net (code "172") (name "UJIDEVICE6") (class "Default")
      (node (ref "D37") (pin "C") (pinfunction "K_C") (pintype "passive"))
      (node (ref "D7") (pin "C") (pinfunction "K_C") (pintype "passive"))
      (node (ref "LED6") (pin "A") (pinfunction "A_A") (pintype "passive"))
    )
    (net (code "173") (name "UJIDEVICE7") (class "Default")
      (node (ref "D38") (pin "C") (pinfunction "K_C") (pintype "passive"))
      (node (ref "D8") (pin "C") (pinfunction "K_C") (pintype "passive"))
      (node (ref "LED7") (pin "A") (pinfunction "A_A") (pintype "passive"))
    )
    (net (code "174") (name "UJIDEVICE8") (class "Default")
      (node (ref "D39") (pin "C") (pinfunction "K_C") (pintype "passive"))
      (node (ref "D9") (pin "C") (pinfunction "K_C") (pintype "passive"))
      (node (ref "LED8") (pin "A") (pinfunction "A_A") (pintype "passive"))
    )
    (net (code "175") (name "UJIDEVICE9") (class "Default")
      (node (ref "D10") (pin "C") (pinfunction "K_C") (pintype "passive"))
      (node (ref "D40") (pin "C") (pinfunction "K_C") (pintype "passive"))
      (node (ref "LED9") (pin "A") (pinfunction "A_A") (pintype "passive"))
    )
    (net (code "176") (name "UJIDEVICE10") (class "Default")
      (node (ref "D11") (pin "C") (pinfunction "K_C") (pintype "passive"))
      (node (ref "D41") (pin "C") (pinfunction "K_C") (pintype "passive"))
      (node (ref "LED10") (pin "A") (pinfunction "A_A") (pintype "passive"))
    )
    (net (code "177") (name "UJIDEVICE11") (class "Default")
      (node (ref "D12") (pin "C") (pinfunction "K_C") (pintype "passive"))
      (node (ref "D42") (pin "C") (pinfunction "K_C") (pintype "passive"))
      (node (ref "LED11") (pin "A") (pinfunction "A_A") (pintype "passive"))
    )
    (net (code "178") (name "UJIDEVICE12") (class "Default")
      (node (ref "D13") (pin "C") (pinfunction "K_C") (pintype "passive"))
      (node (ref "D43") (pin "C") (pinfunction "K_C") (pintype "passive"))
      (node (ref "LED12") (pin "A") (pinfunction "A_A") (pintype "passive"))
    )
    (net (code "179") (name "UJIDEVICE13") (class "Default")
      (node (ref "D14") (pin "C") (pinfunction "K_C") (pintype "passive"))
      (node (ref "D44") (pin "C") (pinfunction "K_C") (pintype "passive"))
      (node (ref "LED13") (pin "A") (pinfunction "A_A") (pintype "passive"))
    )
    (net (code "180") (name "UJIDEVICE14") (class "Default")
      (node (ref "D15") (pin "C") (pinfunction "K_C") (pintype "passive"))
      (node (ref "D45") (pin "C") (pinfunction "K_C") (pintype "passive"))
      (node (ref "LED14") (pin "A") (pinfunction "A_A") (pintype "passive"))
    )
    (net (code "181") (name "UJIDEVICE15") (class "Default")
      (node (ref "D16") (pin "C") (pinfunction "K_C") (pintype "passive"))
      (node (ref "D46") (pin "C") (pinfunction "K_C") (pintype "passive"))
      (node (ref "LED15") (pin "A") (pinfunction "A_A") (pintype "passive"))
    )
    (net (code "182") (name "UJIDEVICE16") (class "Default")
      (node (ref "D17") (pin "C") (pinfunction "K_C") (pintype "passive"))
      (node (ref "D47") (pin "C") (pinfunction "K_C") (pintype "passive"))
      (node (ref "LED16") (pin "A") (pinfunction "A_A") (pintype "passive"))
    )
    (net (code "183") (name "UJIDEVICE17") (class "Default")
      (node (ref "D18") (pin "C") (pinfunction "K_C") (pintype "passive"))
      (node (ref "D48") (pin "C") (pinfunction "K_C") (pintype "passive"))
      (node (ref "LED17") (pin "A") (pinfunction "A_A") (pintype "passive"))
    )
    (net (code "184") (name "UJIDEVICE18") (class "Default")
      (node (ref "D19") (pin "C") (pinfunction "K_C") (pintype "passive"))
      (node (ref "D49") (pin "C") (pinfunction "K_C") (pintype "passive"))
      (node (ref "LED18") (pin "A") (pinfunction "A_A") (pintype "passive"))
    )
    (net (code "185") (name "UJIDEVICE19") (class "Default")
      (node (ref "D20") (pin "C") (pinfunction "K_C") (pintype "passive"))
      (node (ref "D50") (pin "C") (pinfunction "K_C") (pintype "passive"))
      (node (ref "LED19") (pin "A") (pinfunction "A_A") (pintype "passive"))
    )
    (net (code "186") (name "UJIDEVICE20") (class "Default")
      (node (ref "D21") (pin "C") (pinfunction "K_C") (pintype "passive"))
      (node (ref "D51") (pin "C") (pinfunction "K_C") (pintype "passive"))
      (node (ref "LED20") (pin "A") (pinfunction "A_A") (pintype "passive"))
    )
    (net (code "187") (name "UJIDEVICE21") (class "Default")
      (node (ref "D22") (pin "C") (pinfunction "K_C") (pintype "passive"))
      (node (ref "D52") (pin "C") (pinfunction "K_C") (pintype "passive"))
      (node (ref "LED21") (pin "A") (pinfunction "A_A") (pintype "passive"))
    )
    (net (code "188") (name "UJIDEVICE22") (class "Default")
      (node (ref "D23") (pin "C") (pinfunction "K_C") (pintype "passive"))
      (node (ref "D53") (pin "C") (pinfunction "K_C") (pintype "passive"))
      (node (ref "LED22") (pin "A") (pinfunction "A_A") (pintype "passive"))
    )
    (net (code "189") (name "UJIDEVICE23") (class "Default")
      (node (ref "D24") (pin "C") (pinfunction "K_C") (pintype "passive"))
      (node (ref "D54") (pin "C") (pinfunction "K_C") (pintype "passive"))
      (node (ref "LED23") (pin "A") (pinfunction "A_A") (pintype "passive"))
    )
    (net (code "190") (name "UJIDEVICE24") (class "Default")
      (node (ref "D25") (pin "C") (pinfunction "K_C") (pintype "passive"))
      (node (ref "D55") (pin "C") (pinfunction "K_C") (pintype "passive"))
      (node (ref "LED24") (pin "A") (pinfunction "A_A") (pintype "passive"))
    )
    (net (code "191") (name "USB_N") (class "Default")
      (node (ref "J1") (pin "2") (pinfunction "D-_2") (pintype "passive"))
      (node (ref "U1") (pin "6") (pinfunction "UD-_6") (pintype "bidirectional"))
    )
    (net (code "192") (name "USB_P") (class "Default")
      (node (ref "J1") (pin "3") (pinfunction "D+_3") (pintype "passive"))
      (node (ref "U1") (pin "5") (pinfunction "UD+_5") (pintype "bidirectional"))
    )
    (net (code "193") (name "VCC") (class "Default")
      (node (ref "C9") (pin "2") (pinfunction "2_2") (pintype "passive"))
      (node (ref "IC1") (pin "9") (pinfunction "VDD_9") (pintype "power_in"))
      (node (ref "IC4") (pin "9") (pinfunction "VDD_9") (pintype "power_in"))
      (node (ref "JP1") (pin "2") (pinfunction "2_2") (pintype "passive"))
      (node (ref "R100") (pin "2") (pinfunction "2_2") (pintype "passive"))
      (node (ref "R103") (pin "1") (pinfunction "1_1") (pintype "passive"))
      (node (ref "R107") (pin "2") (pinfunction "2_2") (pintype "passive"))
      (node (ref "R108") (pin "1") (pinfunction "1_1") (pintype "passive"))
      (node (ref "R27") (pin "2") (pinfunction "2_2") (pintype "passive"))
      (node (ref "R28") (pin "2") (pinfunction "2_2") (pintype "passive"))
      (node (ref "R29") (pin "2") (pinfunction "2_2") (pintype "passive"))
      (node (ref "R30") (pin "2") (pinfunction "2_2") (pintype "passive"))
      (node (ref "R49") (pin "2") (pinfunction "2_2") (pintype "passive"))
      (node (ref "R50") (pin "2") (pinfunction "2_2") (pintype "passive"))
      (node (ref "R51") (pin "2") (pinfunction "2_2") (pintype "passive"))
      (node (ref "R52") (pin "2") (pinfunction "2_2") (pintype "passive"))
      (node (ref "R53") (pin "2") (pinfunction "2_2") (pintype "passive"))
      (node (ref "R54") (pin "2") (pinfunction "2_2") (pintype "passive"))
      (node (ref "R55") (pin "2") (pinfunction "2_2") (pintype "passive"))
      (node (ref "R56") (pin "2") (pinfunction "2_2") (pintype "passive"))
      (node (ref "R57") (pin "2") (pinfunction "2_2") (pintype "passive"))
      (node (ref "R58") (pin "2") (pinfunction "2_2") (pintype "passive"))
      (node (ref "R59") (pin "2") (pinfunction "2_2") (pintype "passive"))
      (node (ref "R60") (pin "2") (pinfunction "2_2") (pintype "passive"))
      (node (ref "R61") (pin "2") (pinfunction "2_2") (pintype "passive"))
      (node (ref "R62") (pin "2") (pinfunction "2_2") (pintype "passive"))
      (node (ref "R63") (pin "2") (pinfunction "2_2") (pintype "passive"))
      (node (ref "R64") (pin "2") (pinfunction "2_2") (pintype "passive"))
      (node (ref "R65") (pin "2") (pinfunction "2_2") (pintype "passive"))
      (node (ref "R66") (pin "2") (pinfunction "2_2") (pintype "passive"))
      (node (ref "R67") (pin "2") (pinfunction "2_2") (pintype "passive"))
      (node (ref "R68") (pin "2") (pinfunction "2_2") (pintype "passive"))
      (node (ref "R69") (pin "2") (pinfunction "2_2") (pintype "passive"))
      (node (ref "R70") (pin "2") (pinfunction "2_2") (pintype "passive"))
      (node (ref "R71") (pin "2") (pinfunction "2_2") (pintype "passive"))
      (node (ref "R72") (pin "2") (pinfunction "2_2") (pintype "passive"))
      (node (ref "R97") (pin "2") (pinfunction "2_2") (pintype "passive"))
      (node (ref "R98") (pin "2") (pinfunction "2_2") (pintype "passive"))
      (node (ref "R99") (pin "2") (pinfunction "2_2") (pintype "passive"))
      (node (ref "U$1") (pin "3V3") (pinfunction "3V3_3V3") (pintype "bidirectional"))
      (node (ref "U$1") (pin "3V3.2") (pinfunction "3V3.2_3V3.2") (pintype "bidirectional"))
      (node (ref "U2") (pin "2") (pinfunction "VOUT_2") (pintype "output"))
      (node (ref "U2") (pin "4") (pinfunction "VOUT_4") (pintype "output"))
      (node (ref "U3") (pin "2") (pinfunction "3V3_2") (pintype "power_in"))
    )
    (net (code "194") (name "VUSB") (class "Default")
      (node (ref "C3") (pin "+") (pinfunction "+_+") (pintype "passive"))
      (node (ref "C4") (pin "2") (pinfunction "2_2") (pintype "passive"))
      (node (ref "D27") (pin "A") (pinfunction "A_A") (pintype "passive"))
      (node (ref "J1") (pin "1") (pinfunction "VUSB_1") (pintype "passive"))
      (node (ref "U1") (pin "16") (pinfunction "VCC_16") (pintype "power_in"))
    )
    (net (code "195") (name "unconnected-(IC1-GPB0-Pad1)") (class "Default")
      (node (ref "IC1") (pin "1") (pinfunction "GPB0_1") (pintype "bidirectional"))
    )
    (net (code "196") (name "unconnected-(IC1-GPB1-Pad2)") (class "Default")
      (node (ref "IC1") (pin "2") (pinfunction "GPB1_2") (pintype "bidirectional"))
    )
    (net (code "197") (name "unconnected-(IC1-GPB2-Pad3)") (class "Default")
      (node (ref "IC1") (pin "3") (pinfunction "GPB2_3") (pintype "bidirectional"))
    )
    (net (code "198") (name "unconnected-(IC1-GPB3-Pad4)") (class "Default")
      (node (ref "IC1") (pin "4") (pinfunction "GPB3_4") (pintype "bidirectional"))
    )
    (net (code "199") (name "unconnected-(IC1-GPB4-Pad5)") (class "Default")
      (node (ref "IC1") (pin "5") (pinfunction "GPB4_5") (pintype "bidirectional"))
    )
    (net (code "200") (name "unconnected-(IC1-GPB5-Pad6)") (class "Default")
      (node (ref "IC1") (pin "6") (pinfunction "GPB5_6") (pintype "bidirectional"))
    )
    (net (code "201") (name "unconnected-(IC1-GPB6-Pad7)") (class "Default")
      (node (ref "IC1") (pin "7") (pinfunction "GPB6_7") (pintype "bidirectional"))
    )
    (net (code "202") (name "unconnected-(IC1-GPB7-Pad8)") (class "Default")
      (node (ref "IC1") (pin "8") (pinfunction "GPB7_8") (pintype "bidirectional"))
    )
    (net (code "203") (name "unconnected-(IC1-INTA-Pad20)") (class "Default")
      (node (ref "IC1") (pin "20") (pinfunction "INTA_20") (pintype "output"))
    )
    (net (code "204") (name "unconnected-(IC1-INTB-Pad19)") (class "Default")
      (node (ref "IC1") (pin "19") (pinfunction "INTB_19") (pintype "output"))
    )
    (net (code "205") (name "unconnected-(IC4-INTA-Pad20)") (class "Default")
      (node (ref "IC4") (pin "20") (pinfunction "INTA_20") (pintype "output"))
    )
    (net (code "206") (name "unconnected-(IC4-INTB-Pad19)") (class "Default")
      (node (ref "IC4") (pin "19") (pinfunction "INTB_19") (pintype "output"))
    )
    (net (code "207") (name "unconnected-(J1-ID-Pad4)") (class "Default")
      (node (ref "J1") (pin "4") (pinfunction "ID_4") (pintype "passive"))
    )
    (net (code "208") (name "unconnected-(JP1-Pad5)") (class "Default")
      (node (ref "JP1") (pin "5") (pinfunction "5_5") (pintype "passive"))
    )
    (net (code "209") (name "unconnected-(JP1-Pad6)") (class "Default")
      (node (ref "JP1") (pin "6") (pinfunction "6_6") (pintype "passive"))
    )
    (net (code "210") (name "unconnected-(K2C-O-PadO2)") (class "Default")
      (node (ref "K2") (pin "O2") (pinfunction "O_O2") (pintype "passive"))
    )
    (net (code "211") (name "unconnected-(K2C-P-PadP2)") (class "Default")
      (node (ref "K2") (pin "P2") (pinfunction "P_P2") (pintype "passive"))
    )
    (net (code "212") (name "unconnected-(K2C-S-PadS2)") (class "Default")
      (node (ref "K2") (pin "S2") (pinfunction "S_S2") (pintype "passive"))
    )
    (net (code "213") (name "unconnected-(U$1-PadNC)") (class "Default")
      (node (ref "U$1") (pin "NC") (pinfunction "NC_NC") (pintype "bidirectional"))
    )
    (net (code "214") (name "unconnected-(U$1-PadRST)") (class "Default")
      (node (ref "U$1") (pin "RST") (pinfunction "RST_RST") (pintype "bidirectional"))
    )
    (net (code "215") (name "unconnected-(U1-RS232-Pad15)") (class "Default")
      (node (ref "U1") (pin "15") (pinfunction "RS232_15") (pintype "input"))
    )
    (net (code "216") (name "unconnected-(U1-~{CTS}-Pad9)") (class "Default")
      (node (ref "U1") (pin "9") (pinfunction "~{CTS}_9") (pintype "input"))
    )
    (net (code "217") (name "unconnected-(U1-~{DCD}-Pad12)") (class "Default")
      (node (ref "U1") (pin "12") (pinfunction "~{DCD}_12") (pintype "input"))
    )
    (net (code "218") (name "unconnected-(U1-~{DSR}-Pad10)") (class "Default")
      (node (ref "U1") (pin "10") (pinfunction "~{DSR}_10") (pintype "input"))
    )
    (net (code "219") (name "unconnected-(U1-~{RI}-Pad11)") (class "Default")
      (node (ref "U1") (pin "11") (pinfunction "~{RI}_11") (pintype "input"))
    )
    (net (code "220") (name "unconnected-(U3-IO2-Pad24)") (class "Default")
      (node (ref "U3") (pin "24") (pinfunction "IO2_24") (pintype "bidirectional"))
    )
    (net (code "221") (name "unconnected-(U3-IO14-Pad13)") (class "Default")
      (node (ref "U3") (pin "13") (pinfunction "IO14_13") (pintype "bidirectional"))
    )
    (net (code "222") (name "unconnected-(U3-IO15-Pad23)") (class "Default")
      (node (ref "U3") (pin "23") (pinfunction "IO15_23") (pintype "bidirectional"))
    )
    (net (code "223") (name "unconnected-(U3-IO33-Pad9)") (class "Default")
      (node (ref "U3") (pin "9") (pinfunction "IO33_9") (pintype "bidirectional"))
    )
    (net (code "224") (name "unconnected-(U3-IO34-Pad6)") (class "Default")
      (node (ref "U3") (pin "6") (pinfunction "IO34_6") (pintype "input"))
    )
    (net (code "225") (name "unconnected-(U3-IO35-Pad7)") (class "Default")
      (node (ref "U3") (pin "7") (pinfunction "IO35_7") (pintype "input"))
    )
    (net (code "226") (name "unconnected-(U3-SCK{slash}CLK-Pad20)") (class "Default")
      (node (ref "U3") (pin "20") (pinfunction "SCK/CLK_20") (pintype "bidirectional"))
    )
    (net (code "227") (name "unconnected-(U3-SCS{slash}CMD-Pad19)") (class "Default")
      (node (ref "U3") (pin "19") (pinfunction "SCS/CMD_19") (pintype "bidirectional"))
    )
    (net (code "228") (name "unconnected-(U3-SDI{slash}SD1-Pad22)") (class "Default")
      (node (ref "U3") (pin "22") (pinfunction "SDI/SD1_22") (pintype "bidirectional"))
    )
    (net (code "229") (name "unconnected-(U3-SDO{slash}SD0-Pad21)") (class "Default")
      (node (ref "U3") (pin "21") (pinfunction "SDO/SD0_21") (pintype "bidirectional"))
    )
    (net (code "230") (name "unconnected-(U3-SENSOR_VN-Pad5)") (class "Default")
      (node (ref "U3") (pin "5") (pinfunction "SENSOR_VN_5") (pintype "input"))
    )
    (net (code "231") (name "unconnected-(U3-SENSOR_VP-Pad4)") (class "Default")
      (node (ref "U3") (pin "4") (pinfunction "SENSOR_VP_4") (pintype "input"))
    )
    (net (code "232") (name "unconnected-(U3-SHD{slash}SD2-Pad17)") (class "Default")
      (node (ref "U3") (pin "17") (pinfunction "SHD/SD2_17") (pintype "bidirectional"))
    )
    (net (code "233") (name "unconnected-(U3-SWP{slash}SD3-Pad18)") (class "Default")
      (node (ref "U3") (pin "18") (pinfunction "SWP/SD3_18") (pintype "bidirectional"))
    )
  )
)
